# canSlaveV03_16s.net
KiCad netlist of a schematic drawn in EAGLE
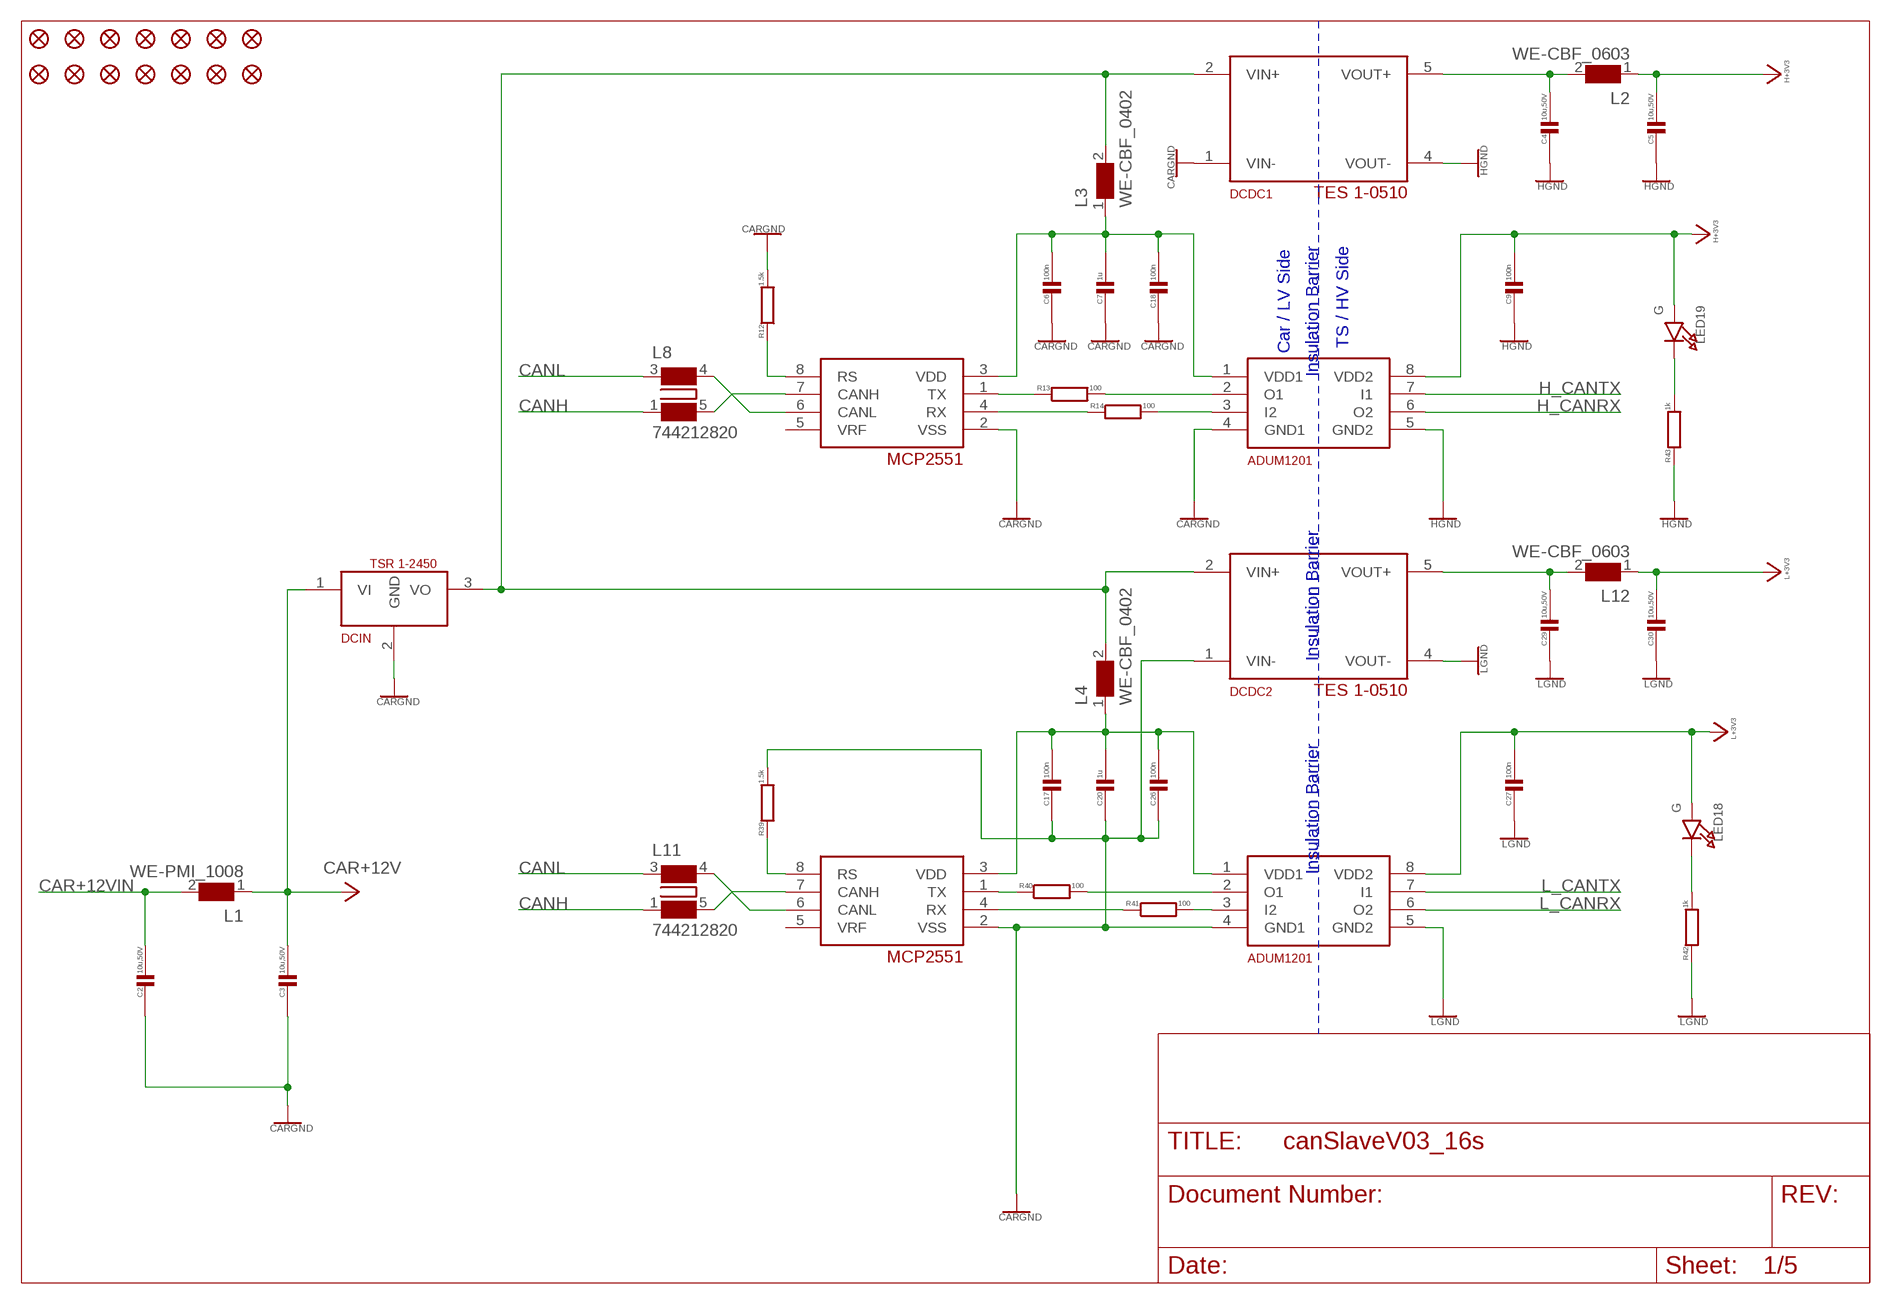
[diagram p0: schematic, sheet 1]
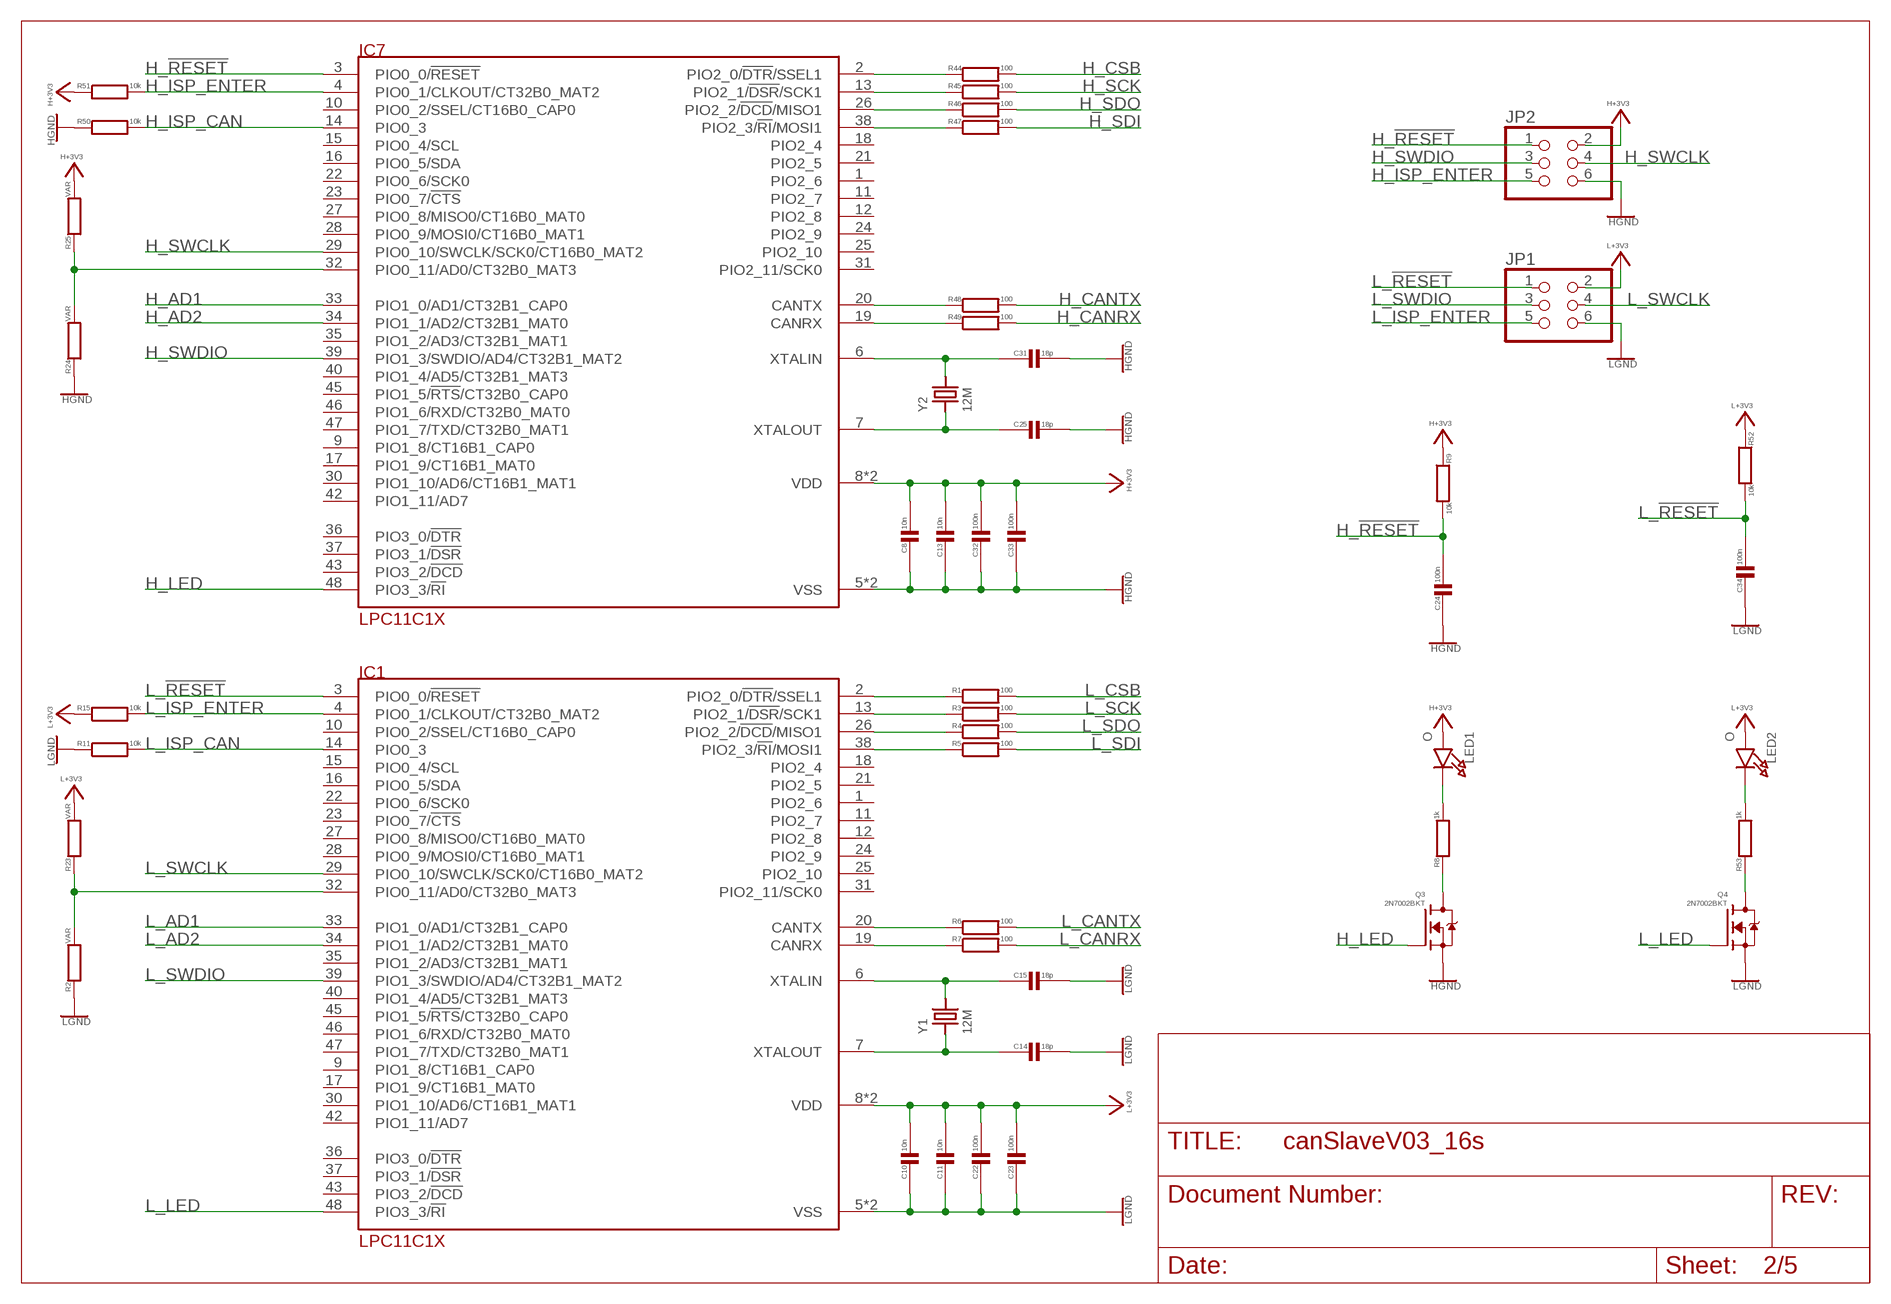
[diagram p1: schematic, sheet 2]
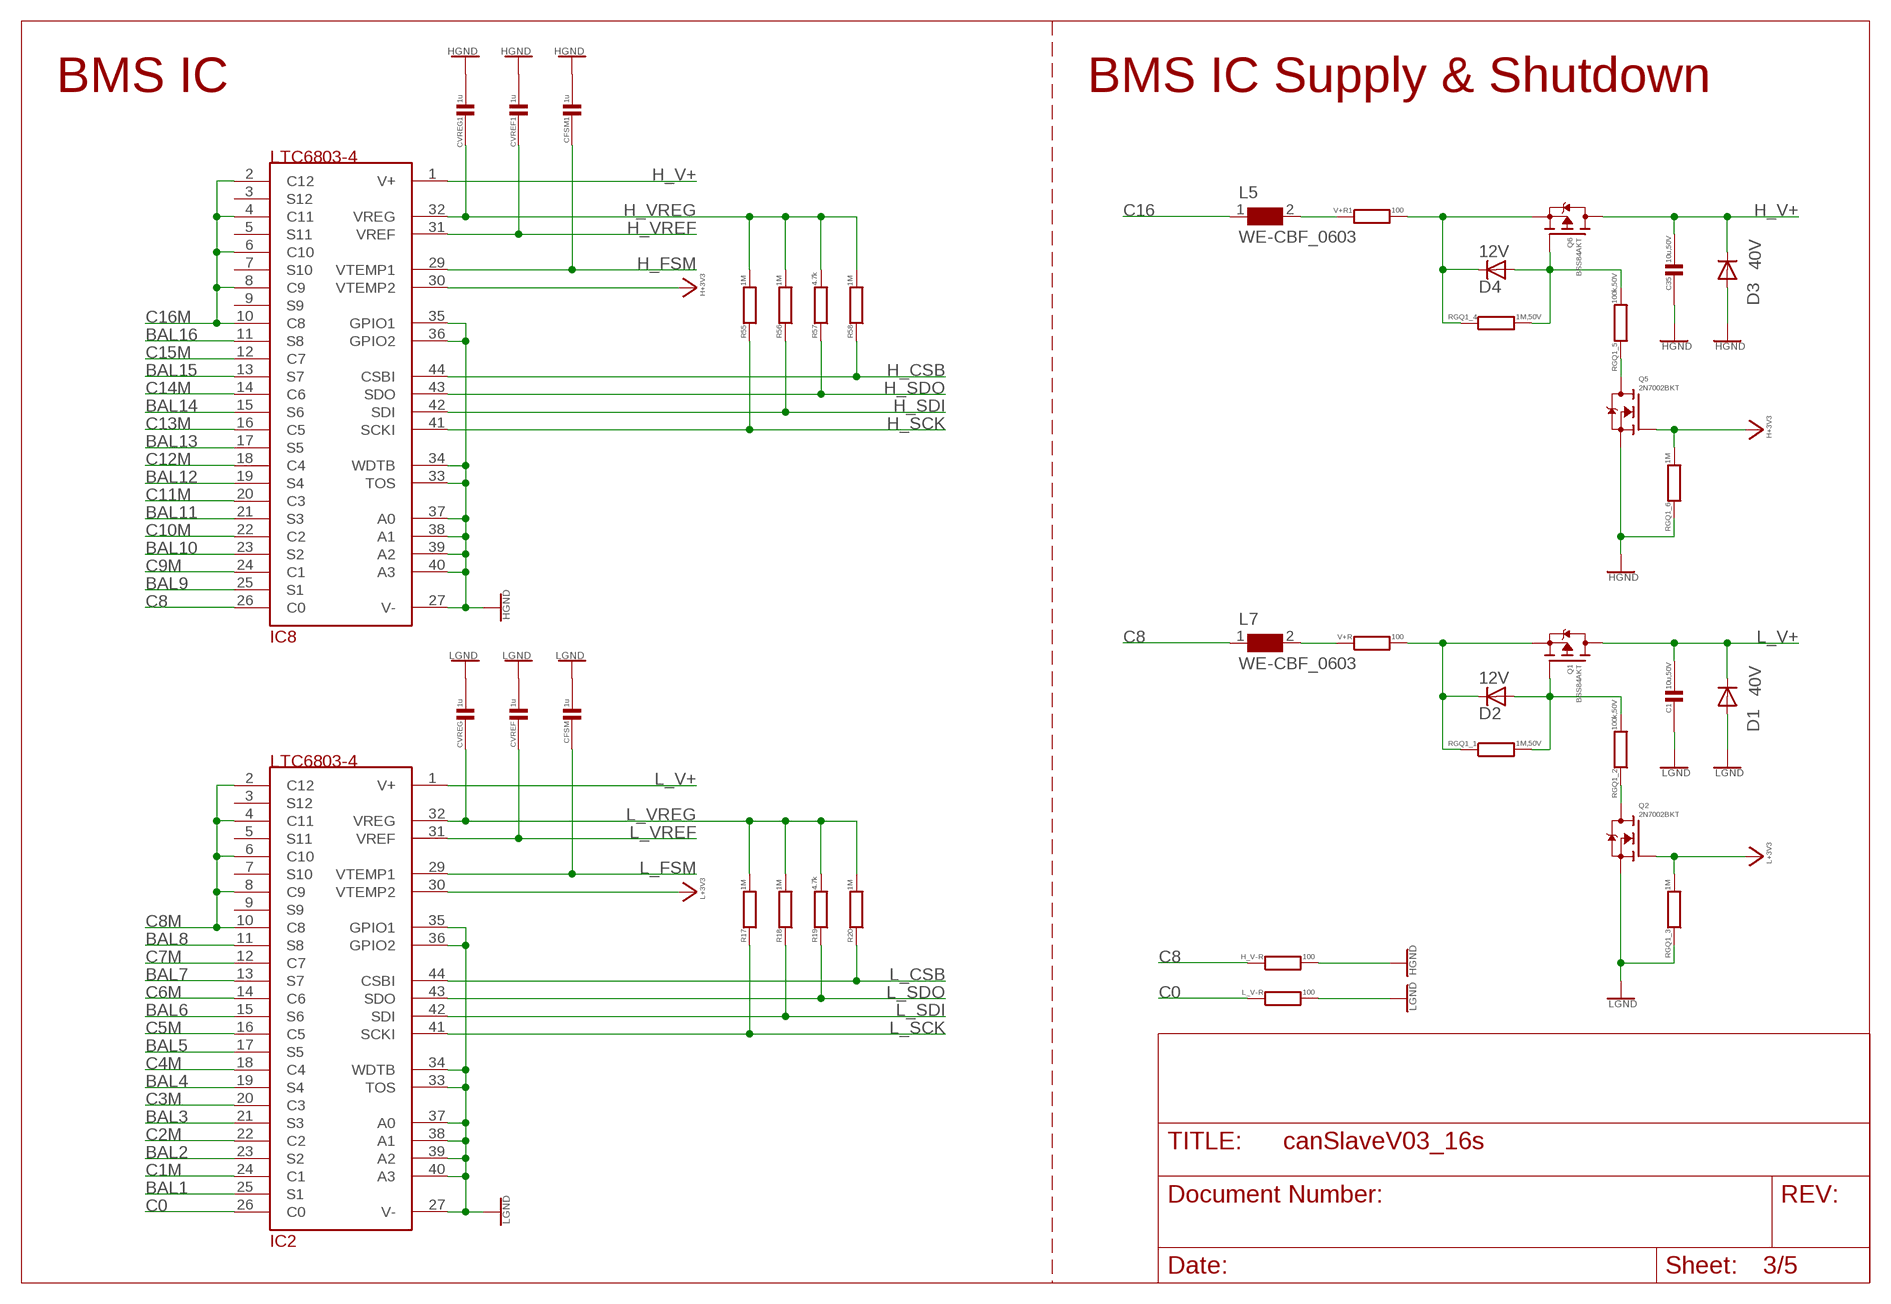
[diagram p2: schematic, sheet 3]
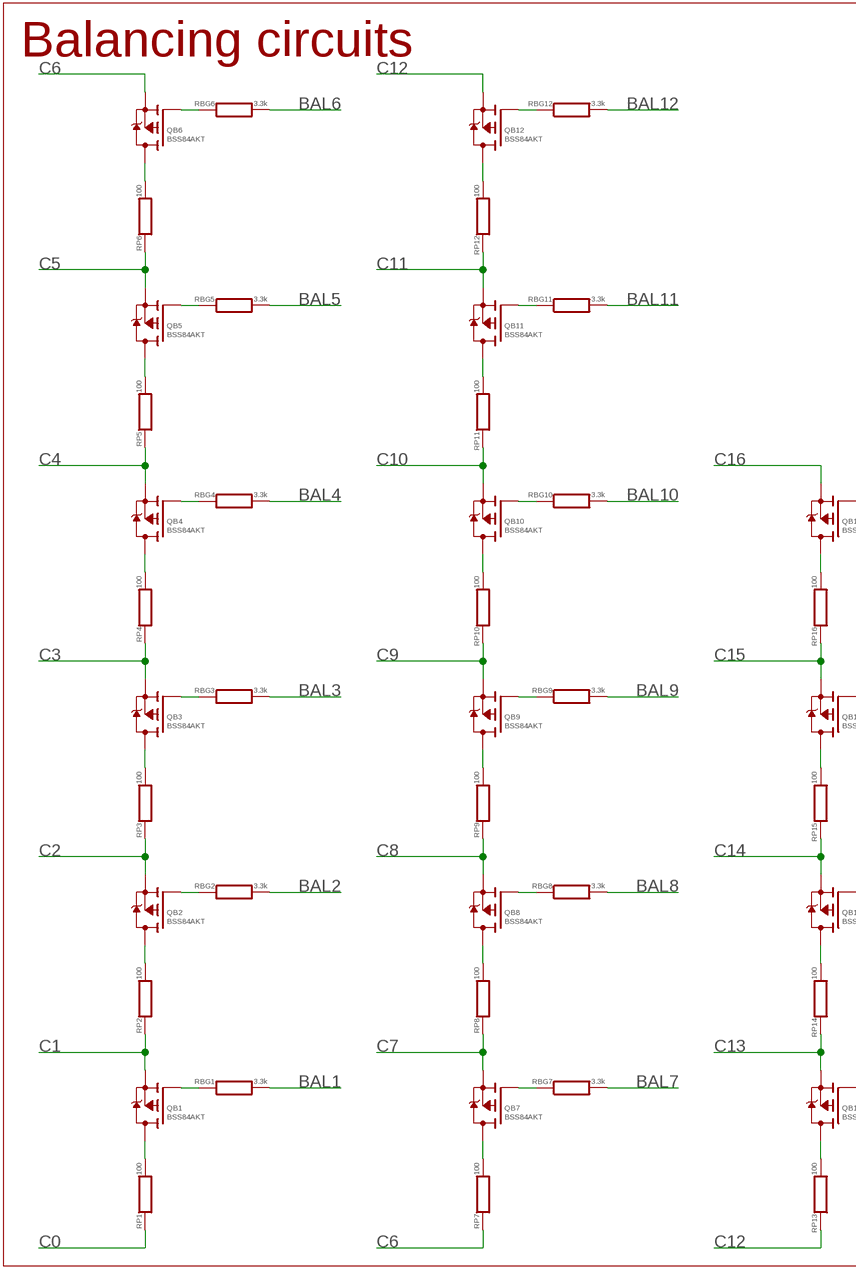
[diagram p3: schematic, sheet 4, part 1 of 2]
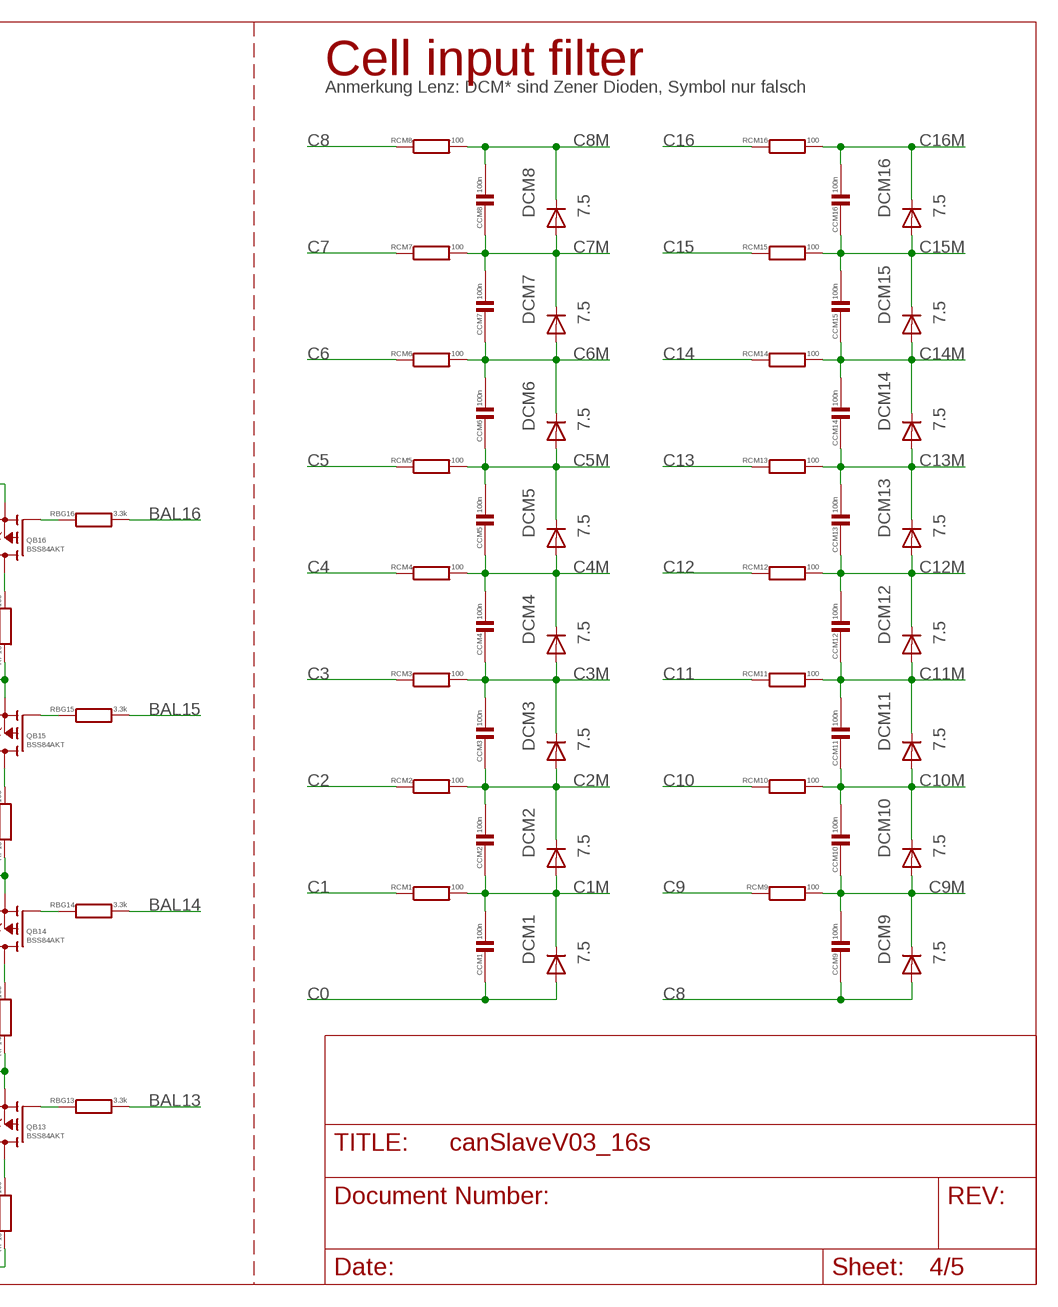
[diagram p4: schematic, sheet 4, part 2 of 2]
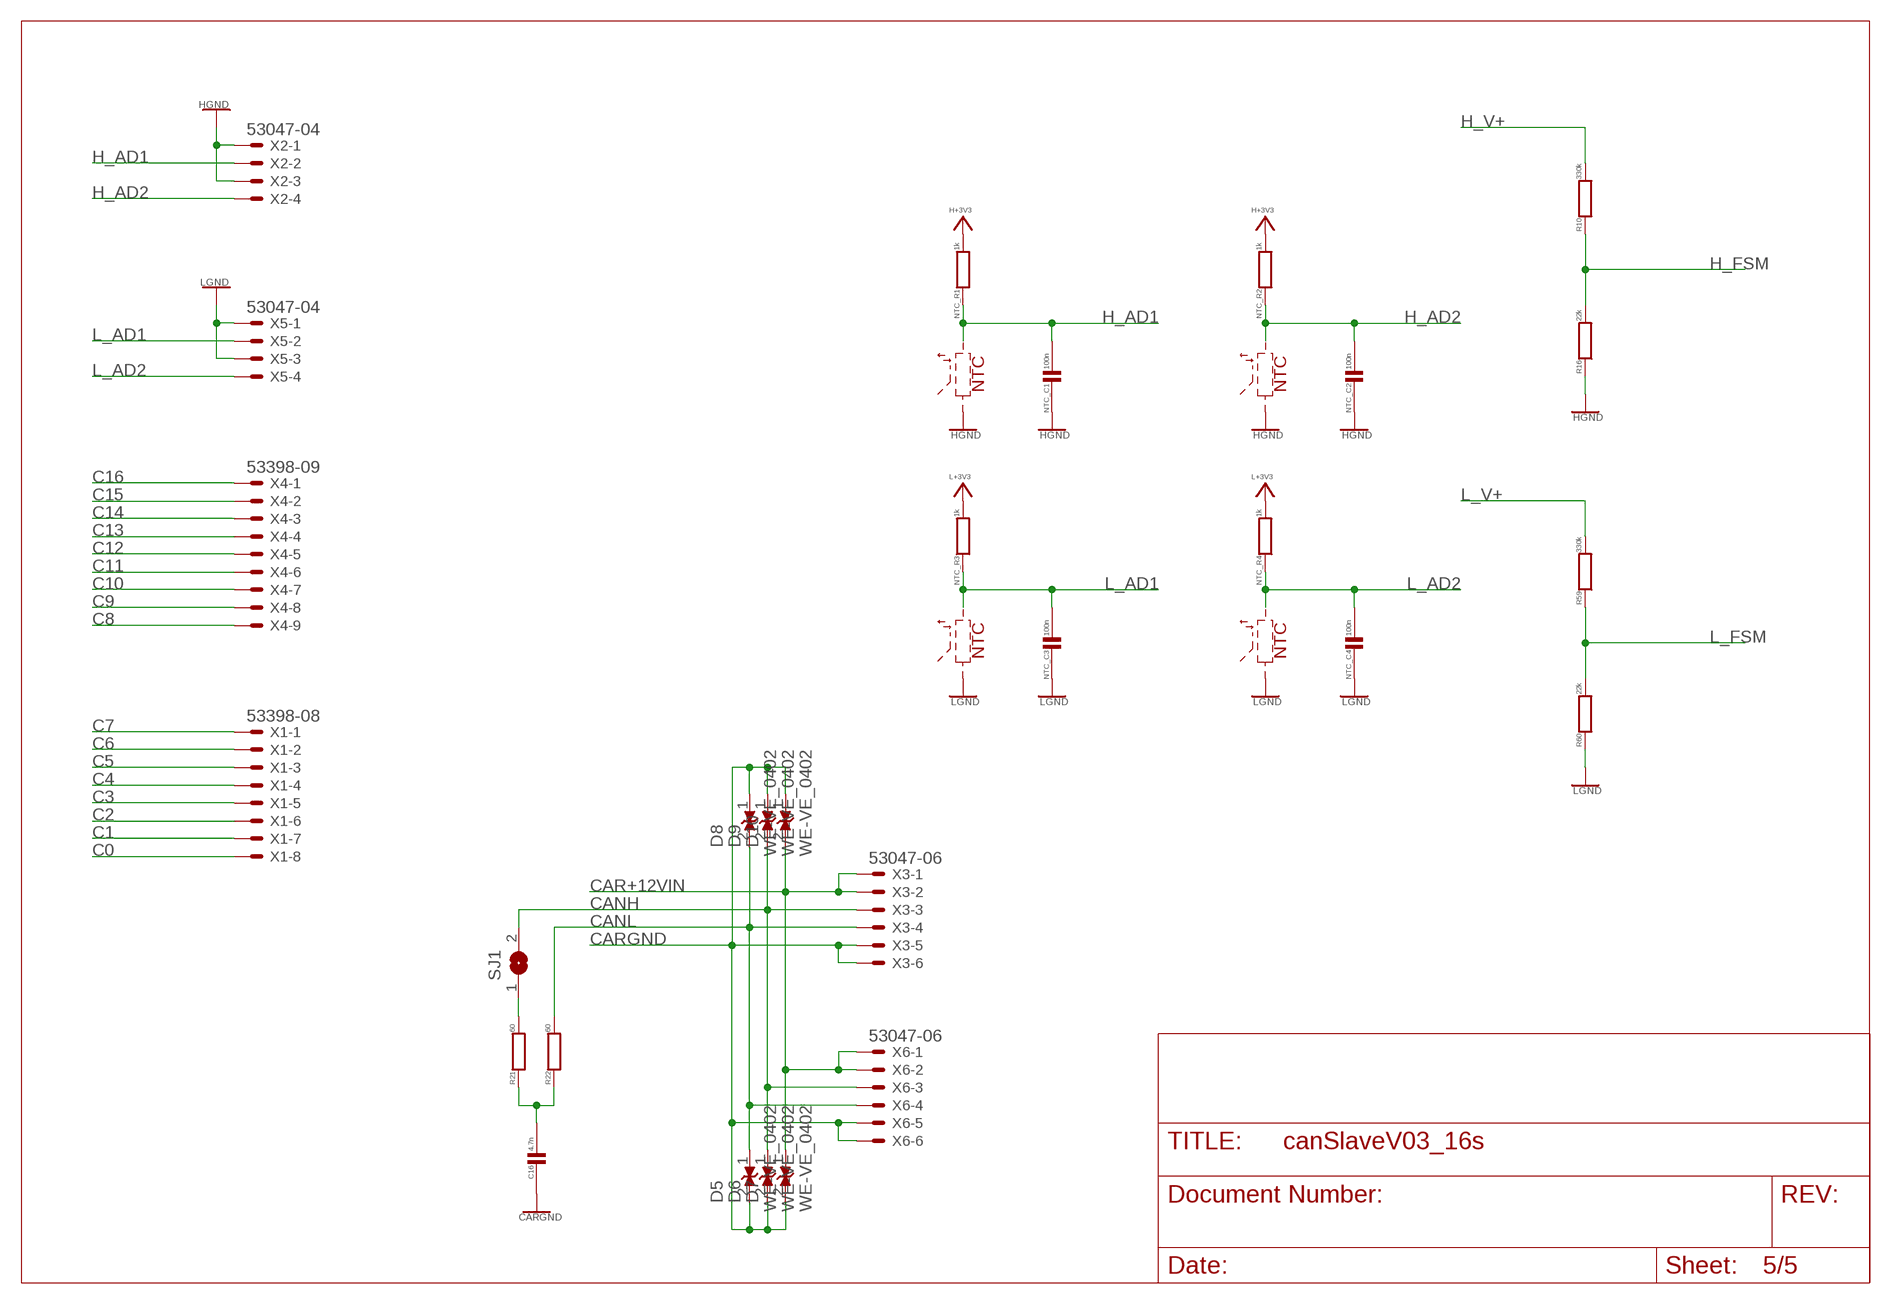
[diagram p5: schematic, sheet 5]

(export (version "E")
  (design (tool "Eeschema 10.0.6"))
  (components
    (comp (ref "C1")
      (value "10u,50V")
      (footprint "eagle-import:C1206")
      (libsource (lib "eagle-import") (part "C1206"))
    )
    (comp (ref "C35")
      (value "10u,50V")
      (footprint "eagle-import:C1206")
      (libsource (lib "eagle-import") (part "C1206"))
    )
    (comp (ref "CFSM")
      (value "1u")
      (footprint "eagle-import:C0402")
      (libsource (lib "eagle-import") (part "C0402"))
    )
    (comp (ref "CFSM1")
      (value "1u")
      (footprint "eagle-import:C0402")
      (libsource (lib "eagle-import") (part "C0402"))
    )
    (comp (ref "CVREF")
      (value "1u")
      (footprint "eagle-import:C0402")
      (libsource (lib "eagle-import") (part "C0402"))
    )
    (comp (ref "CVREF1")
      (value "1u")
      (footprint "eagle-import:C0402")
      (libsource (lib "eagle-import") (part "C0402"))
    )
    (comp (ref "CVREG")
      (value "1u")
      (footprint "eagle-import:C0402")
      (libsource (lib "eagle-import") (part "C0402"))
    )
    (comp (ref "CVREG1")
      (value "1u")
      (footprint "eagle-import:C0402")
      (libsource (lib "eagle-import") (part "C0402"))
    )
    (comp (ref "D1")
      (value "40V")
      (footprint "eagle-import:SOD323-R")
      (libsource (lib "eagle-import") (part "DIODE-SOD323-R"))
    )
    (comp (ref "D2")
      (value "12V")
      (footprint "eagle-import:SOD323-R")
      (libsource (lib "eagle-import") (part "DIODE-SOD323-R"))
    )
    (comp (ref "D3")
      (value "40V")
      (footprint "eagle-import:SOD323-R")
      (libsource (lib "eagle-import") (part "DIODE-SOD323-R"))
    )
    (comp (ref "D4")
      (value "12V")
      (footprint "eagle-import:SOD323-R")
      (libsource (lib "eagle-import") (part "DIODE-SOD323-R"))
    )
    (comp (ref "H_V-R")
      (value "100")
      (footprint "eagle-import:R0402")
      (libsource (lib "eagle-import") (part "R0402"))
    )
    (comp (ref "IC2")
      (value "LTC6803-4")
      (footprint "eagle-import:44SSOP")
      (libsource (lib "eagle-import") (part "LTC6803-4"))
    )
    (comp (ref "IC8")
      (value "LTC6803-4")
      (footprint "eagle-import:44SSOP")
      (libsource (lib "eagle-import") (part "LTC6803-4"))
    )
    (comp (ref "L5")
      (value "WE-CBF_0603")
      (footprint "eagle-import:0603")
      (libsource (lib "eagle-import") (part "WE-CBF_0603"))
    )
    (comp (ref "L7")
      (value "WE-CBF_0603")
      (footprint "eagle-import:0603")
      (libsource (lib "eagle-import") (part "WE-CBF_0603"))
    )
    (comp (ref "L_V-R")
      (value "100")
      (footprint "eagle-import:R0402")
      (libsource (lib "eagle-import") (part "R0402"))
    )
    (comp (ref "Q1")
      (value "BSS84AKT")
      (footprint "eagle-import:SOT416")
      (libsource (lib "eagle-import") (part "BSS84AKT"))
    )
    (comp (ref "Q2")
      (value "2N7002BKT")
      (footprint "eagle-import:SOT416")
      (libsource (lib "eagle-import") (part "2N7002BKT"))
    )
    (comp (ref "Q5")
      (value "2N7002BKT")
      (footprint "eagle-import:SOT416")
      (libsource (lib "eagle-import") (part "2N7002BKT"))
    )
    (comp (ref "Q6")
      (value "BSS84AKT")
      (footprint "eagle-import:SOT416")
      (libsource (lib "eagle-import") (part "BSS84AKT"))
    )
    (comp (ref "R17")
      (value "1M")
      (footprint "eagle-import:R0402")
      (libsource (lib "eagle-import") (part "R0402"))
    )
    (comp (ref "R18")
      (value "1M")
      (footprint "eagle-import:R0402")
      (libsource (lib "eagle-import") (part "R0402"))
    )
    (comp (ref "R19")
      (value "4.7k")
      (footprint "eagle-import:R0402")
      (libsource (lib "eagle-import") (part "R0402"))
    )
    (comp (ref "R20")
      (value "1M")
      (footprint "eagle-import:R0402")
      (libsource (lib "eagle-import") (part "R0402"))
    )
    (comp (ref "R55")
      (value "1M")
      (footprint "eagle-import:R0402")
      (libsource (lib "eagle-import") (part "R0402"))
    )
    (comp (ref "R56")
      (value "1M")
      (footprint "eagle-import:R0402")
      (libsource (lib "eagle-import") (part "R0402"))
    )
    (comp (ref "R57")
      (value "4.7k")
      (footprint "eagle-import:R0402")
      (libsource (lib "eagle-import") (part "R0402"))
    )
    (comp (ref "R58")
      (value "1M")
      (footprint "eagle-import:R0402")
      (libsource (lib "eagle-import") (part "R0402"))
    )
    (comp (ref "RGQ1_1")
      (value "1M,50V")
      (footprint "eagle-import:R0603")
      (libsource (lib "eagle-import") (part "R0603"))
    )
    (comp (ref "RGQ1_2")
      (value "100k,50V")
      (footprint "eagle-import:R0603")
      (libsource (lib "eagle-import") (part "R0603"))
    )
    (comp (ref "RGQ1_3")
      (value "1M")
      (footprint "eagle-import:R0402")
      (libsource (lib "eagle-import") (part "R0402"))
    )
    (comp (ref "RGQ1_4")
      (value "1M,50V")
      (footprint "eagle-import:R0603")
      (libsource (lib "eagle-import") (part "R0603"))
    )
    (comp (ref "RGQ1_5")
      (value "100k,50V")
      (footprint "eagle-import:R0603")
      (libsource (lib "eagle-import") (part "R0603"))
    )
    (comp (ref "RGQ1_6")
      (value "1M")
      (footprint "eagle-import:R0402")
      (libsource (lib "eagle-import") (part "R0402"))
    )
    (comp (ref "V+R")
      (value "100")
      (footprint "eagle-import:R0402")
      (libsource (lib "eagle-import") (part "R0402"))
    )
    (comp (ref "V+R1")
      (value "100")
      (footprint "eagle-import:R0402")
      (libsource (lib "eagle-import") (part "R0402"))
    )
    (comp (ref "C8")
      (value "10n")
      (footprint "eagle-import:C0402")
      (libsource (lib "eagle-import") (part "C0402"))
    )
    (comp (ref "C10")
      (value "10n")
      (footprint "eagle-import:C0402")
      (libsource (lib "eagle-import") (part "C0402"))
    )
    (comp (ref "C11")
      (value "10n")
      (footprint "eagle-import:C0402")
      (libsource (lib "eagle-import") (part "C0402"))
    )
    (comp (ref "C13")
      (value "10n")
      (footprint "eagle-import:C0402")
      (libsource (lib "eagle-import") (part "C0402"))
    )
    (comp (ref "C14")
      (value "18p")
      (footprint "eagle-import:C0402")
      (libsource (lib "eagle-import") (part "C0402"))
    )
    (comp (ref "C15")
      (value "18p")
      (footprint "eagle-import:C0402")
      (libsource (lib "eagle-import") (part "C0402"))
    )
    (comp (ref "C22")
      (value "100n")
      (footprint "eagle-import:C0402")
      (libsource (lib "eagle-import") (part "C0402"))
    )
    (comp (ref "C23")
      (value "100n")
      (footprint "eagle-import:C0402")
      (libsource (lib "eagle-import") (part "C0402"))
    )
    (comp (ref "C24")
      (value "100n")
      (footprint "eagle-import:C0402")
      (libsource (lib "eagle-import") (part "C0402"))
    )
    (comp (ref "C25")
      (value "18p")
      (footprint "eagle-import:C0402")
      (libsource (lib "eagle-import") (part "C0402"))
    )
    (comp (ref "C31")
      (value "18p")
      (footprint "eagle-import:C0402")
      (libsource (lib "eagle-import") (part "C0402"))
    )
    (comp (ref "C32")
      (value "100n")
      (footprint "eagle-import:C0402")
      (libsource (lib "eagle-import") (part "C0402"))
    )
    (comp (ref "C33")
      (value "100n")
      (footprint "eagle-import:C0402")
      (libsource (lib "eagle-import") (part "C0402"))
    )
    (comp (ref "C34")
      (value "100n")
      (footprint "eagle-import:C0402")
      (libsource (lib "eagle-import") (part "C0402"))
    )
    (comp (ref "IC1")
      (value "LPC11C1X")
      (footprint "eagle-import:LQFP48")
      (libsource (lib "eagle-import") (part "LPC11C1X"))
    )
    (comp (ref "IC7")
      (value "LPC11C1X")
      (footprint "eagle-import:LQFP48")
      (libsource (lib "eagle-import") (part "LPC11C1X"))
    )
    (comp (ref "JP1")
      (value "HEADER-2X31.27")
      (footprint "eagle-import:2X03_1.27MM_SMT")
      (libsource (lib "eagle-import") (part "HEADER-2X31.27"))
    )
    (comp (ref "JP2")
      (value "HEADER-2X31.27")
      (footprint "eagle-import:2X03_1.27MM_SMT")
      (libsource (lib "eagle-import") (part "HEADER-2X31.27"))
    )
    (comp (ref "LED1")
      (value "O")
      (footprint "eagle-import:CHIPLED_0603")
      (libsource (lib "eagle-import") (part "LED0603"))
    )
    (comp (ref "LED2")
      (value "O")
      (footprint "eagle-import:CHIPLED_0603")
      (libsource (lib "eagle-import") (part "LED0603"))
    )
    (comp (ref "Q3")
      (value "2N7002BKT")
      (footprint "eagle-import:SOT416")
      (libsource (lib "eagle-import") (part "2N7002BKT"))
    )
    (comp (ref "Q4")
      (value "2N7002BKT")
      (footprint "eagle-import:SOT416")
      (libsource (lib "eagle-import") (part "2N7002BKT"))
    )
    (comp (ref "R1")
      (value "100")
      (footprint "eagle-import:R0402")
      (libsource (lib "eagle-import") (part "R0402"))
    )
    (comp (ref "R2")
      (value "VAR")
      (footprint "eagle-import:R0402")
      (libsource (lib "eagle-import") (part "R0402"))
    )
    (comp (ref "R3")
      (value "100")
      (footprint "eagle-import:R0402")
      (libsource (lib "eagle-import") (part "R0402"))
    )
    (comp (ref "R4")
      (value "100")
      (footprint "eagle-import:R0402")
      (libsource (lib "eagle-import") (part "R0402"))
    )
    (comp (ref "R5")
      (value "100")
      (footprint "eagle-import:R0402")
      (libsource (lib "eagle-import") (part "R0402"))
    )
    (comp (ref "R6")
      (value "100")
      (footprint "eagle-import:R0402")
      (libsource (lib "eagle-import") (part "R0402"))
    )
    (comp (ref "R7")
      (value "100")
      (footprint "eagle-import:R0402")
      (libsource (lib "eagle-import") (part "R0402"))
    )
    (comp (ref "R8")
      (value "1k")
      (footprint "eagle-import:R0603")
      (libsource (lib "eagle-import") (part "R0603"))
    )
    (comp (ref "R9")
      (value "10k")
      (footprint "eagle-import:R0402")
      (libsource (lib "eagle-import") (part "R0402"))
    )
    (comp (ref "R11")
      (value "10k")
      (footprint "eagle-import:R0402")
      (libsource (lib "eagle-import") (part "R0402"))
    )
    (comp (ref "R15")
      (value "10k")
      (footprint "eagle-import:R0402")
      (libsource (lib "eagle-import") (part "R0402"))
    )
    (comp (ref "R23")
      (value "VAR")
      (footprint "eagle-import:R0402")
      (libsource (lib "eagle-import") (part "R0402"))
    )
    (comp (ref "R24")
      (value "VAR")
      (footprint "eagle-import:R0402")
      (libsource (lib "eagle-import") (part "R0402"))
    )
    (comp (ref "R25")
      (value "VAR")
      (footprint "eagle-import:R0402")
      (libsource (lib "eagle-import") (part "R0402"))
    )
    (comp (ref "R44")
      (value "100")
      (footprint "eagle-import:R0402")
      (libsource (lib "eagle-import") (part "R0402"))
    )
    (comp (ref "R45")
      (value "100")
      (footprint "eagle-import:R0402")
      (libsource (lib "eagle-import") (part "R0402"))
    )
    (comp (ref "R46")
      (value "100")
      (footprint "eagle-import:R0402")
      (libsource (lib "eagle-import") (part "R0402"))
    )
    (comp (ref "R47")
      (value "100")
      (footprint "eagle-import:R0402")
      (libsource (lib "eagle-import") (part "R0402"))
    )
    (comp (ref "R48")
      (value "100")
      (footprint "eagle-import:R0402")
      (libsource (lib "eagle-import") (part "R0402"))
    )
    (comp (ref "R49")
      (value "100")
      (footprint "eagle-import:R0402")
      (libsource (lib "eagle-import") (part "R0402"))
    )
    (comp (ref "R50")
      (value "10k")
      (footprint "eagle-import:R0402")
      (libsource (lib "eagle-import") (part "R0402"))
    )
    (comp (ref "R51")
      (value "10k")
      (footprint "eagle-import:R0402")
      (libsource (lib "eagle-import") (part "R0402"))
    )
    (comp (ref "R52")
      (value "10k")
      (footprint "eagle-import:R0402")
      (libsource (lib "eagle-import") (part "R0402"))
    )
    (comp (ref "R53")
      (value "1k")
      (footprint "eagle-import:R0603")
      (libsource (lib "eagle-import") (part "R0603"))
    )
    (comp (ref "Y1")
      (value "12M")
      (footprint "eagle-import:CRYSTAL_3.2X2.5")
      (libsource (lib "eagle-import") (part "CRYSTALTHIN"))
    )
    (comp (ref "Y2")
      (value "12M")
      (footprint "eagle-import:CRYSTAL_3.2X2.5")
      (libsource (lib "eagle-import") (part "CRYSTALTHIN"))
    )
    (comp (ref "C16")
      (value "4.7n")
      (footprint "eagle-import:C0402")
      (libsource (lib "eagle-import") (part "C0402"))
    )
    (comp (ref "D5")
      (value "WE-VE_0402")
      (footprint "eagle-import:WESURGE_0402")
      (libsource (lib "eagle-import") (part "WE-VE_0402"))
    )
    (comp (ref "D6")
      (value "WE-VE_0402")
      (footprint "eagle-import:WESURGE_0402")
      (libsource (lib "eagle-import") (part "WE-VE_0402"))
    )
    (comp (ref "D7")
      (value "WE-VE_0402")
      (footprint "eagle-import:WESURGE_0402")
      (libsource (lib "eagle-import") (part "WE-VE_0402"))
    )
    (comp (ref "D8")
      (value "WE-VE_0402")
      (footprint "eagle-import:WESURGE_0402")
      (libsource (lib "eagle-import") (part "WE-VE_0402"))
    )
    (comp (ref "D9")
      (value "WE-VE_0402")
      (footprint "eagle-import:WESURGE_0402")
      (libsource (lib "eagle-import") (part "WE-VE_0402"))
    )
    (comp (ref "D10")
      (value "WE-VE_0402")
      (footprint "eagle-import:WESURGE_0402")
      (libsource (lib "eagle-import") (part "WE-VE_0402"))
    )
    (comp (ref "NTC_C1")
      (value "100n")
      (footprint "eagle-import:C0402")
      (libsource (lib "eagle-import") (part "C0402"))
    )
    (comp (ref "NTC_C2")
      (value "100n")
      (footprint "eagle-import:C0402")
      (libsource (lib "eagle-import") (part "C0402"))
    )
    (comp (ref "NTC_C3")
      (value "100n")
      (footprint "eagle-import:C0402")
      (libsource (lib "eagle-import") (part "C0402"))
    )
    (comp (ref "NTC_C4")
      (value "100n")
      (footprint "eagle-import:C0402")
      (libsource (lib "eagle-import") (part "C0402"))
    )
    (comp (ref "NTC_R1")
      (value "1k")
      (footprint "eagle-import:R0402")
      (libsource (lib "eagle-import") (part "R0402"))
    )
    (comp (ref "NTC_R2")
      (value "1k")
      (footprint "eagle-import:R0402")
      (libsource (lib "eagle-import") (part "R0402"))
    )
    (comp (ref "NTC_R3")
      (value "1k")
      (footprint "eagle-import:R0402")
      (libsource (lib "eagle-import") (part "R0402"))
    )
    (comp (ref "NTC_R4")
      (value "1k")
      (footprint "eagle-import:R0402")
      (libsource (lib "eagle-import") (part "R0402"))
    )
    (comp (ref "R10")
      (value "330k")
      (footprint "eagle-import:R0603")
      (libsource (lib "eagle-import") (part "R0603"))
    )
    (comp (ref "R16")
      (value "22k")
      (footprint "eagle-import:R0603")
      (libsource (lib "eagle-import") (part "R0603"))
    )
    (comp (ref "R21")
      (value "60")
      (footprint "eagle-import:R0402")
      (libsource (lib "eagle-import") (part "R0402"))
    )
    (comp (ref "R22")
      (value "60")
      (footprint "eagle-import:R0402")
      (libsource (lib "eagle-import") (part "R0402"))
    )
    (comp (ref "R59")
      (value "330k")
      (footprint "eagle-import:R0603")
      (libsource (lib "eagle-import") (part "R0603"))
    )
    (comp (ref "R60")
      (value "22k")
      (footprint "eagle-import:R0603")
      (libsource (lib "eagle-import") (part "R0603"))
    )
    (comp (ref "SJ1")
      (value "SOLDERJUMPERSMALL")
      (footprint "eagle-import:SOLDERJUMPER_REFLOW_NOPASTE_SMALL")
      (libsource (lib "eagle-import") (part "SOLDERJUMPERSMALL"))
    )
    (comp (ref "X1")
      (value "53398-08")
      (footprint "eagle-import:53398-08")
      (libsource (lib "eagle-import") (part "53?-08398"))
    )
    (comp (ref "X2")
      (value "53047-04")
      (footprint "eagle-import:53047-04")
      (fields
        (field (name "MF") "WALDOM/MOLEX")
        (field (name "MPN") "53047-0410")
        (field (name "MF_1") "WALDOM/MOLEX")
        (field (name "MPN_1") "53047-0410")
        (field (name "OC_FARNELL") "9733060")
        (field (name "OC_NEWARK") "38C9900")
      )
      (libsource (lib "eagle-import") (part "53?-04047"))
    )
    (comp (ref "X3")
      (value "53047-06")
      (footprint "eagle-import:53047-06")
      (fields (field (name "MPN") "53047-0610-C"))
      (libsource (lib "eagle-import") (part "53?-06047"))
    )
    (comp (ref "X4")
      (value "53398-09")
      (footprint "eagle-import:53398-09")
      (libsource (lib "eagle-import") (part "53?-09398"))
    )
    (comp (ref "X5")
      (value "53047-04")
      (footprint "eagle-import:53047-04")
      (fields
        (field (name "MF") "WALDOM/MOLEX")
        (field (name "MPN") "53047-0410")
        (field (name "MF_1") "WALDOM/MOLEX")
        (field (name "MPN_1") "53047-0410")
        (field (name "OC_FARNELL") "9733060")
        (field (name "OC_NEWARK") "38C9900")
      )
      (libsource (lib "eagle-import") (part "53?-04047"))
    )
    (comp (ref "X6")
      (value "53047-06")
      (footprint "eagle-import:53047-06")
      (fields (field (name "MPN") "53047-0610-C"))
      (libsource (lib "eagle-import") (part "53?-06047"))
    )
    (comp (ref "C2")
      (value "10u,50V")
      (footprint "eagle-import:C0603")
      (libsource (lib "eagle-import") (part "C0603"))
    )
    (comp (ref "C3")
      (value "10u,50V")
      (footprint "eagle-import:C0603")
      (libsource (lib "eagle-import") (part "C0603"))
    )
    (comp (ref "C4")
      (value "10u,50V")
      (footprint "eagle-import:C0603")
      (libsource (lib "eagle-import") (part "C0603"))
    )
    (comp (ref "C5")
      (value "10u,50V")
      (footprint "eagle-import:C0603")
      (libsource (lib "eagle-import") (part "C0603"))
    )
    (comp (ref "C6")
      (value "100n")
      (footprint "eagle-import:C0402")
      (libsource (lib "eagle-import") (part "C0402"))
    )
    (comp (ref "C7")
      (value "1u")
      (footprint "eagle-import:C0402")
      (libsource (lib "eagle-import") (part "C0402"))
    )
    (comp (ref "C9")
      (value "100n")
      (footprint "eagle-import:C0402")
      (libsource (lib "eagle-import") (part "C0402"))
    )
    (comp (ref "C17")
      (value "100n")
      (footprint "eagle-import:C0402")
      (libsource (lib "eagle-import") (part "C0402"))
    )
    (comp (ref "C18")
      (value "100n")
      (footprint "eagle-import:C0402")
      (libsource (lib "eagle-import") (part "C0402"))
    )
    (comp (ref "C20")
      (value "1u")
      (footprint "eagle-import:C0402")
      (libsource (lib "eagle-import") (part "C0402"))
    )
    (comp (ref "C26")
      (value "100n")
      (footprint "eagle-import:C0402")
      (libsource (lib "eagle-import") (part "C0402"))
    )
    (comp (ref "C27")
      (value "100n")
      (footprint "eagle-import:C0402")
      (libsource (lib "eagle-import") (part "C0402"))
    )
    (comp (ref "C29")
      (value "10u,50V")
      (footprint "eagle-import:C0603")
      (libsource (lib "eagle-import") (part "C0603"))
    )
    (comp (ref "C30")
      (value "10u,50V")
      (footprint "eagle-import:C0603")
      (libsource (lib "eagle-import") (part "C0603"))
    )
    (comp (ref "DCDC1")
      (value "TES 1-0510")
      (footprint "eagle-import:ISF")
      (libsource (lib "eagle-import") (part "ISFXXXXA"))
    )
    (comp (ref "DCDC2")
      (value "TES 1-0510")
      (footprint "eagle-import:ISF")
      (libsource (lib "eagle-import") (part "ISFXXXXA"))
    )
    (comp (ref "DCIN")
      (value "TSR 1-2450")
      (footprint "eagle-import:TSR1")
      (libsource (lib "eagle-import") (part "TSR1"))
    )
    (comp (ref "FID1")
      (value "FIDUCIAL\"\"")
      (footprint "eagle-import:FIDUCIAL_1MM")
      (libsource (lib "eagle-import") (part "FIDUCIAL{dblquote}{dblquote}"))
    )
    (comp (ref "FID2")
      (value "FIDUCIAL\"\"")
      (footprint "eagle-import:FIDUCIAL_1MM")
      (libsource (lib "eagle-import") (part "FIDUCIAL{dblquote}{dblquote}"))
    )
    (comp (ref "FID3")
      (value "FIDUCIAL\"\"")
      (footprint "eagle-import:FIDUCIAL_1MM")
      (libsource (lib "eagle-import") (part "FIDUCIAL{dblquote}{dblquote}"))
    )
    (comp (ref "FID4")
      (value "FIDUCIAL\"\"")
      (footprint "eagle-import:FIDUCIAL_1MM")
      (libsource (lib "eagle-import") (part "FIDUCIAL{dblquote}{dblquote}"))
    )
    (comp (ref "FID5")
      (value "FIDUCIAL\"\"")
      (footprint "eagle-import:FIDUCIAL_1MM")
      (libsource (lib "eagle-import") (part "FIDUCIAL{dblquote}{dblquote}"))
    )
    (comp (ref "FID6")
      (value "FIDUCIAL\"\"")
      (footprint "eagle-import:FIDUCIAL_1MM")
      (libsource (lib "eagle-import") (part "FIDUCIAL{dblquote}{dblquote}"))
    )
    (comp (ref "FID7")
      (value "FIDUCIAL\"\"")
      (footprint "eagle-import:FIDUCIAL_1MM")
      (libsource (lib "eagle-import") (part "FIDUCIAL{dblquote}{dblquote}"))
    )
    (comp (ref "FID8")
      (value "FIDUCIAL\"\"")
      (footprint "eagle-import:FIDUCIAL_1MM")
      (libsource (lib "eagle-import") (part "FIDUCIAL{dblquote}{dblquote}"))
    )
    (comp (ref "FID9")
      (value "FIDUCIAL\"\"")
      (footprint "eagle-import:FIDUCIAL_1MM")
      (libsource (lib "eagle-import") (part "FIDUCIAL{dblquote}{dblquote}"))
    )
    (comp (ref "FID10")
      (value "FIDUCIAL\"\"")
      (footprint "eagle-import:FIDUCIAL_1MM")
      (libsource (lib "eagle-import") (part "FIDUCIAL{dblquote}{dblquote}"))
    )
    (comp (ref "FID11")
      (value "FIDUCIAL\"\"")
      (footprint "eagle-import:FIDUCIAL_1MM")
      (libsource (lib "eagle-import") (part "FIDUCIAL{dblquote}{dblquote}"))
    )
    (comp (ref "FID12")
      (value "FIDUCIAL\"\"")
      (footprint "eagle-import:FIDUCIAL_1MM")
      (libsource (lib "eagle-import") (part "FIDUCIAL{dblquote}{dblquote}"))
    )
    (comp (ref "FID13")
      (value "FIDUCIAL\"\"")
      (footprint "eagle-import:FIDUCIAL_1MM")
      (libsource (lib "eagle-import") (part "FIDUCIAL{dblquote}{dblquote}"))
    )
    (comp (ref "FID14")
      (value "FIDUCIAL\"\"")
      (footprint "eagle-import:FIDUCIAL_1MM")
      (libsource (lib "eagle-import") (part "FIDUCIAL{dblquote}{dblquote}"))
    )
    (comp (ref "IC3")
      (value "ADUM1201")
      (footprint "eagle-import:SO-8")
      (libsource (lib "eagle-import") (part "ADUM1201"))
    )
    (comp (ref "IC4")
      (value "MCP2551")
      (footprint "eagle-import:SO-8")
      (libsource (lib "eagle-import") (part "MCP2551"))
    )
    (comp (ref "IC5")
      (value "MCP2551")
      (footprint "eagle-import:SO-8")
      (libsource (lib "eagle-import") (part "MCP2551"))
    )
    (comp (ref "IC6")
      (value "ADUM1201")
      (footprint "eagle-import:SO-8")
      (libsource (lib "eagle-import") (part "ADUM1201"))
    )
    (comp (ref "L1")
      (value "WE-PMI_1008")
      (footprint "eagle-import:WE-PMI_1008")
      (libsource (lib "eagle-import") (part "WE-PMI_1008"))
    )
    (comp (ref "L2")
      (value "WE-CBF_0603")
      (footprint "eagle-import:0603")
      (libsource (lib "eagle-import") (part "WE-CBF_0603"))
    )
    (comp (ref "L3")
      (value "WE-CBF_0402")
      (footprint "eagle-import:0402")
      (libsource (lib "eagle-import") (part "WE-CBF_0402"))
    )
    (comp (ref "L4")
      (value "WE-CBF_0402")
      (footprint "eagle-import:0402")
      (libsource (lib "eagle-import") (part "WE-CBF_0402"))
    )
    (comp (ref "L8")
      (value "744212820")
      (footprint "eagle-import:WE-SL1")
      (libsource (lib "eagle-import") (part "WE-SL1"))
    )
    (comp (ref "L11")
      (value "744212820")
      (footprint "eagle-import:WE-SL1")
      (libsource (lib "eagle-import") (part "WE-SL1"))
    )
    (comp (ref "L12")
      (value "WE-CBF_0603")
      (footprint "eagle-import:0603")
      (libsource (lib "eagle-import") (part "WE-CBF_0603"))
    )
    (comp (ref "LED18")
      (value "G")
      (footprint "eagle-import:CHIPLED_0603")
      (libsource (lib "eagle-import") (part "LED0603"))
    )
    (comp (ref "LED19")
      (value "G")
      (footprint "eagle-import:CHIPLED_0603")
      (libsource (lib "eagle-import") (part "LED0603"))
    )
    (comp (ref "R12")
      (value "1.5k")
      (footprint "eagle-import:R0402")
      (libsource (lib "eagle-import") (part "R0402"))
    )
    (comp (ref "R13")
      (value "100")
      (footprint "eagle-import:R0402")
      (libsource (lib "eagle-import") (part "R0402"))
    )
    (comp (ref "R14")
      (value "100")
      (footprint "eagle-import:R0402")
      (libsource (lib "eagle-import") (part "R0402"))
    )
    (comp (ref "R39")
      (value "1.5k")
      (footprint "eagle-import:R0402")
      (libsource (lib "eagle-import") (part "R0402"))
    )
    (comp (ref "R40")
      (value "100")
      (footprint "eagle-import:R0402")
      (libsource (lib "eagle-import") (part "R0402"))
    )
    (comp (ref "R41")
      (value "100")
      (footprint "eagle-import:R0402")
      (libsource (lib "eagle-import") (part "R0402"))
    )
    (comp (ref "R42")
      (value "1k")
      (footprint "eagle-import:R0603")
      (libsource (lib "eagle-import") (part "R0603"))
    )
    (comp (ref "R43")
      (value "1k")
      (footprint "eagle-import:R0603")
      (libsource (lib "eagle-import") (part "R0603"))
    )
    (comp (ref "CCM1")
      (value "100n")
      (footprint "eagle-import:C0402")
      (libsource (lib "eagle-import") (part "C0402"))
    )
    (comp (ref "CCM2")
      (value "100n")
      (footprint "eagle-import:C0402")
      (libsource (lib "eagle-import") (part "C0402"))
    )
    (comp (ref "CCM3")
      (value "100n")
      (footprint "eagle-import:C0402")
      (libsource (lib "eagle-import") (part "C0402"))
    )
    (comp (ref "CCM4")
      (value "100n")
      (footprint "eagle-import:C0402")
      (libsource (lib "eagle-import") (part "C0402"))
    )
    (comp (ref "CCM5")
      (value "100n")
      (footprint "eagle-import:C0402")
      (libsource (lib "eagle-import") (part "C0402"))
    )
    (comp (ref "CCM6")
      (value "100n")
      (footprint "eagle-import:C0402")
      (libsource (lib "eagle-import") (part "C0402"))
    )
    (comp (ref "CCM7")
      (value "100n")
      (footprint "eagle-import:C0402")
      (libsource (lib "eagle-import") (part "C0402"))
    )
    (comp (ref "CCM8")
      (value "100n")
      (footprint "eagle-import:C0402")
      (libsource (lib "eagle-import") (part "C0402"))
    )
    (comp (ref "CCM9")
      (value "100n")
      (footprint "eagle-import:C0402")
      (libsource (lib "eagle-import") (part "C0402"))
    )
    (comp (ref "CCM10")
      (value "100n")
      (footprint "eagle-import:C0402")
      (libsource (lib "eagle-import") (part "C0402"))
    )
    (comp (ref "CCM11")
      (value "100n")
      (footprint "eagle-import:C0402")
      (libsource (lib "eagle-import") (part "C0402"))
    )
    (comp (ref "CCM12")
      (value "100n")
      (footprint "eagle-import:C0402")
      (libsource (lib "eagle-import") (part "C0402"))
    )
    (comp (ref "CCM13")
      (value "100n")
      (footprint "eagle-import:C0402")
      (libsource (lib "eagle-import") (part "C0402"))
    )
    (comp (ref "CCM14")
      (value "100n")
      (footprint "eagle-import:C0402")
      (libsource (lib "eagle-import") (part "C0402"))
    )
    (comp (ref "CCM15")
      (value "100n")
      (footprint "eagle-import:C0402")
      (libsource (lib "eagle-import") (part "C0402"))
    )
    (comp (ref "CCM16")
      (value "100n")
      (footprint "eagle-import:C0402")
      (libsource (lib "eagle-import") (part "C0402"))
    )
    (comp (ref "DCM1")
      (value "7.5")
      (footprint "eagle-import:SOD323-R")
      (libsource (lib "eagle-import") (part "DIODE-SOD323-R"))
    )
    (comp (ref "DCM2")
      (value "7.5")
      (footprint "eagle-import:SOD323-R")
      (libsource (lib "eagle-import") (part "DIODE-SOD323-R"))
    )
    (comp (ref "DCM3")
      (value "7.5")
      (footprint "eagle-import:SOD323-R")
      (libsource (lib "eagle-import") (part "DIODE-SOD323-R"))
    )
    (comp (ref "DCM4")
      (value "7.5")
      (footprint "eagle-import:SOD323-R")
      (libsource (lib "eagle-import") (part "DIODE-SOD323-R"))
    )
    (comp (ref "DCM5")
      (value "7.5")
      (footprint "eagle-import:SOD323-R")
      (libsource (lib "eagle-import") (part "DIODE-SOD323-R"))
    )
    (comp (ref "DCM6")
      (value "7.5")
      (footprint "eagle-import:SOD323-R")
      (libsource (lib "eagle-import") (part "DIODE-SOD323-R"))
    )
    (comp (ref "DCM7")
      (value "7.5")
      (footprint "eagle-import:SOD323-R")
      (libsource (lib "eagle-import") (part "DIODE-SOD323-R"))
    )
    (comp (ref "DCM8")
      (value "7.5")
      (footprint "eagle-import:SOD323-R")
      (libsource (lib "eagle-import") (part "DIODE-SOD323-R"))
    )
    (comp (ref "DCM9")
      (value "7.5")
      (footprint "eagle-import:SOD323-R")
      (libsource (lib "eagle-import") (part "DIODE-SOD323-R"))
    )
    (comp (ref "DCM10")
      (value "7.5")
      (footprint "eagle-import:SOD323-R")
      (libsource (lib "eagle-import") (part "DIODE-SOD323-R"))
    )
    (comp (ref "DCM11")
      (value "7.5")
      (footprint "eagle-import:SOD323-R")
      (libsource (lib "eagle-import") (part "DIODE-SOD323-R"))
    )
    (comp (ref "DCM12")
      (value "7.5")
      (footprint "eagle-import:SOD323-R")
      (libsource (lib "eagle-import") (part "DIODE-SOD323-R"))
    )
    (comp (ref "DCM13")
      (value "7.5")
      (footprint "eagle-import:SOD323-R")
      (libsource (lib "eagle-import") (part "DIODE-SOD323-R"))
    )
    (comp (ref "DCM14")
      (value "7.5")
      (footprint "eagle-import:SOD323-R")
      (libsource (lib "eagle-import") (part "DIODE-SOD323-R"))
    )
    (comp (ref "DCM15")
      (value "7.5")
      (footprint "eagle-import:SOD323-R")
      (libsource (lib "eagle-import") (part "DIODE-SOD323-R"))
    )
    (comp (ref "DCM16")
      (value "7.5")
      (footprint "eagle-import:SOD323-R")
      (libsource (lib "eagle-import") (part "DIODE-SOD323-R"))
    )
    (comp (ref "QB1")
      (value "BSS84AKT")
      (footprint "eagle-import:SOT416")
      (libsource (lib "eagle-import") (part "BSS84AKT"))
    )
    (comp (ref "QB2")
      (value "BSS84AKT")
      (footprint "eagle-import:SOT416")
      (libsource (lib "eagle-import") (part "BSS84AKT"))
    )
    (comp (ref "QB3")
      (value "BSS84AKT")
      (footprint "eagle-import:SOT416")
      (libsource (lib "eagle-import") (part "BSS84AKT"))
    )
    (comp (ref "QB4")
      (value "BSS84AKT")
      (footprint "eagle-import:SOT416")
      (libsource (lib "eagle-import") (part "BSS84AKT"))
    )
    (comp (ref "QB5")
      (value "BSS84AKT")
      (footprint "eagle-import:SOT416")
      (libsource (lib "eagle-import") (part "BSS84AKT"))
    )
    (comp (ref "QB6")
      (value "BSS84AKT")
      (footprint "eagle-import:SOT416")
      (libsource (lib "eagle-import") (part "BSS84AKT"))
    )
    (comp (ref "QB7")
      (value "BSS84AKT")
      (footprint "eagle-import:SOT416")
      (libsource (lib "eagle-import") (part "BSS84AKT"))
    )
    (comp (ref "QB8")
      (value "BSS84AKT")
      (footprint "eagle-import:SOT416")
      (libsource (lib "eagle-import") (part "BSS84AKT"))
    )
    (comp (ref "QB9")
      (value "BSS84AKT")
      (footprint "eagle-import:SOT416")
      (libsource (lib "eagle-import") (part "BSS84AKT"))
    )
    (comp (ref "QB10")
      (value "BSS84AKT")
      (footprint "eagle-import:SOT416")
      (libsource (lib "eagle-import") (part "BSS84AKT"))
    )
    (comp (ref "QB11")
      (value "BSS84AKT")
      (footprint "eagle-import:SOT416")
      (libsource (lib "eagle-import") (part "BSS84AKT"))
    )
    (comp (ref "QB12")
      (value "BSS84AKT")
      (footprint "eagle-import:SOT416")
      (libsource (lib "eagle-import") (part "BSS84AKT"))
    )
    (comp (ref "QB13")
      (value "BSS84AKT")
      (footprint "eagle-import:SOT416")
      (libsource (lib "eagle-import") (part "BSS84AKT"))
    )
    (comp (ref "QB14")
      (value "BSS84AKT")
      (footprint "eagle-import:SOT416")
      (libsource (lib "eagle-import") (part "BSS84AKT"))
    )
    (comp (ref "QB15")
      (value "BSS84AKT")
      (footprint "eagle-import:SOT416")
      (libsource (lib "eagle-import") (part "BSS84AKT"))
    )
    (comp (ref "QB16")
      (value "BSS84AKT")
      (footprint "eagle-import:SOT416")
      (libsource (lib "eagle-import") (part "BSS84AKT"))
    )
    (comp (ref "RBG1")
      (value "3.3k")
      (footprint "eagle-import:R0402")
      (libsource (lib "eagle-import") (part "R0402"))
    )
    (comp (ref "RBG2")
      (value "3.3k")
      (footprint "eagle-import:R0402")
      (libsource (lib "eagle-import") (part "R0402"))
    )
    (comp (ref "RBG3")
      (value "3.3k")
      (footprint "eagle-import:R0402")
      (libsource (lib "eagle-import") (part "R0402"))
    )
    (comp (ref "RBG4")
      (value "3.3k")
      (footprint "eagle-import:R0402")
      (libsource (lib "eagle-import") (part "R0402"))
    )
    (comp (ref "RBG5")
      (value "3.3k")
      (footprint "eagle-import:R0402")
      (libsource (lib "eagle-import") (part "R0402"))
    )
    (comp (ref "RBG6")
      (value "3.3k")
      (footprint "eagle-import:R0402")
      (libsource (lib "eagle-import") (part "R0402"))
    )
    (comp (ref "RBG7")
      (value "3.3k")
      (footprint "eagle-import:R0402")
      (libsource (lib "eagle-import") (part "R0402"))
    )
    (comp (ref "RBG8")
      (value "3.3k")
      (footprint "eagle-import:R0402")
      (libsource (lib "eagle-import") (part "R0402"))
    )
    (comp (ref "RBG9")
      (value "3.3k")
      (footprint "eagle-import:R0402")
      (libsource (lib "eagle-import") (part "R0402"))
    )
    (comp (ref "RBG10")
      (value "3.3k")
      (footprint "eagle-import:R0402")
      (libsource (lib "eagle-import") (part "R0402"))
    )
    (comp (ref "RBG11")
      (value "3.3k")
      (footprint "eagle-import:R0402")
      (libsource (lib "eagle-import") (part "R0402"))
    )
    (comp (ref "RBG12")
      (value "3.3k")
      (footprint "eagle-import:R0402")
      (libsource (lib "eagle-import") (part "R0402"))
    )
    (comp (ref "RBG13")
      (value "3.3k")
      (footprint "eagle-import:R0402")
      (libsource (lib "eagle-import") (part "R0402"))
    )
    (comp (ref "RBG14")
      (value "3.3k")
      (footprint "eagle-import:R0402")
      (libsource (lib "eagle-import") (part "R0402"))
    )
    (comp (ref "RBG15")
      (value "3.3k")
      (footprint "eagle-import:R0402")
      (libsource (lib "eagle-import") (part "R0402"))
    )
    (comp (ref "RBG16")
      (value "3.3k")
      (footprint "eagle-import:R0402")
      (libsource (lib "eagle-import") (part "R0402"))
    )
    (comp (ref "RCM1")
      (value "100")
      (footprint "eagle-import:R0402")
      (libsource (lib "eagle-import") (part "R0402"))
    )
    (comp (ref "RCM2")
      (value "100")
      (footprint "eagle-import:R0402")
      (libsource (lib "eagle-import") (part "R0402"))
    )
    (comp (ref "RCM3")
      (value "100")
      (footprint "eagle-import:R0402")
      (libsource (lib "eagle-import") (part "R0402"))
    )
    (comp (ref "RCM4")
      (value "100")
      (footprint "eagle-import:R0402")
      (libsource (lib "eagle-import") (part "R0402"))
    )
    (comp (ref "RCM5")
      (value "100")
      (footprint "eagle-import:R0402")
      (libsource (lib "eagle-import") (part "R0402"))
    )
    (comp (ref "RCM6")
      (value "100")
      (footprint "eagle-import:R0402")
      (libsource (lib "eagle-import") (part "R0402"))
    )
    (comp (ref "RCM7")
      (value "100")
      (footprint "eagle-import:R0402")
      (libsource (lib "eagle-import") (part "R0402"))
    )
    (comp (ref "RCM8")
      (value "100")
      (footprint "eagle-import:R0402")
      (libsource (lib "eagle-import") (part "R0402"))
    )
    (comp (ref "RCM9")
      (value "100")
      (footprint "eagle-import:R0402")
      (libsource (lib "eagle-import") (part "R0402"))
    )
    (comp (ref "RCM10")
      (value "100")
      (footprint "eagle-import:R0402")
      (libsource (lib "eagle-import") (part "R0402"))
    )
    (comp (ref "RCM11")
      (value "100")
      (footprint "eagle-import:R0402")
      (libsource (lib "eagle-import") (part "R0402"))
    )
    (comp (ref "RCM12")
      (value "100")
      (footprint "eagle-import:R0402")
      (libsource (lib "eagle-import") (part "R0402"))
    )
    (comp (ref "RCM13")
      (value "100")
      (footprint "eagle-import:R0402")
      (libsource (lib "eagle-import") (part "R0402"))
    )
    (comp (ref "RCM14")
      (value "100")
      (footprint "eagle-import:R0402")
      (libsource (lib "eagle-import") (part "R0402"))
    )
    (comp (ref "RCM15")
      (value "100")
      (footprint "eagle-import:R0402")
      (libsource (lib "eagle-import") (part "R0402"))
    )
    (comp (ref "RCM16")
      (value "100")
      (footprint "eagle-import:R0402")
      (libsource (lib "eagle-import") (part "R0402"))
    )
    (comp (ref "RP1")
      (value "100")
      (footprint "eagle-import:R2512")
      (libsource (lib "eagle-import") (part "R2512"))
    )
    (comp (ref "RP2")
      (value "100")
      (footprint "eagle-import:R2512")
      (libsource (lib "eagle-import") (part "R2512"))
    )
    (comp (ref "RP3")
      (value "100")
      (footprint "eagle-import:R2512")
      (libsource (lib "eagle-import") (part "R2512"))
    )
    (comp (ref "RP4")
      (value "100")
      (footprint "eagle-import:R2512")
      (libsource (lib "eagle-import") (part "R2512"))
    )
    (comp (ref "RP5")
      (value "100")
      (footprint "eagle-import:R2512")
      (libsource (lib "eagle-import") (part "R2512"))
    )
    (comp (ref "RP6")
      (value "100")
      (footprint "eagle-import:R2512")
      (libsource (lib "eagle-import") (part "R2512"))
    )
    (comp (ref "RP7")
      (value "100")
      (footprint "eagle-import:R2512")
      (libsource (lib "eagle-import") (part "R2512"))
    )
    (comp (ref "RP8")
      (value "100")
      (footprint "eagle-import:R2512")
      (libsource (lib "eagle-import") (part "R2512"))
    )
    (comp (ref "RP9")
      (value "100")
      (footprint "eagle-import:R2512")
      (libsource (lib "eagle-import") (part "R2512"))
    )
    (comp (ref "RP10")
      (value "100")
      (footprint "eagle-import:R2512")
      (libsource (lib "eagle-import") (part "R2512"))
    )
    (comp (ref "RP11")
      (value "100")
      (footprint "eagle-import:R2512")
      (libsource (lib "eagle-import") (part "R2512"))
    )
    (comp (ref "RP12")
      (value "100")
      (footprint "eagle-import:R2512")
      (libsource (lib "eagle-import") (part "R2512"))
    )
    (comp (ref "RP13")
      (value "100")
      (footprint "eagle-import:R2512")
      (libsource (lib "eagle-import") (part "R2512"))
    )
    (comp (ref "RP14")
      (value "100")
      (footprint "eagle-import:R2512")
      (libsource (lib "eagle-import") (part "R2512"))
    )
    (comp (ref "RP15")
      (value "100")
      (footprint "eagle-import:R2512")
      (libsource (lib "eagle-import") (part "R2512"))
    )
    (comp (ref "RP16")
      (value "100")
      (footprint "eagle-import:R2512")
      (libsource (lib "eagle-import") (part "R2512"))
    )
  )
  (nets
    (net (code "1") (name "BAL1") (class "Default")
      (node (ref "IC2") (pin "25") (pinfunction "S1_25") (pintype "bidirectional"))
      (node (ref "RBG1") (pin "2") (pinfunction "2_2") (pintype "passive"))
    )
    (net (code "2") (name "BAL2") (class "Default")
      (node (ref "IC2") (pin "23") (pinfunction "S2_23") (pintype "bidirectional"))
      (node (ref "RBG2") (pin "2") (pinfunction "2_2") (pintype "passive"))
    )
    (net (code "3") (name "BAL3") (class "Default")
      (node (ref "IC2") (pin "21") (pinfunction "S3_21") (pintype "bidirectional"))
      (node (ref "RBG3") (pin "2") (pinfunction "2_2") (pintype "passive"))
    )
    (net (code "4") (name "BAL4") (class "Default")
      (node (ref "IC2") (pin "19") (pinfunction "S4_19") (pintype "bidirectional"))
      (node (ref "RBG4") (pin "2") (pinfunction "2_2") (pintype "passive"))
    )
    (net (code "5") (name "BAL5") (class "Default")
      (node (ref "IC2") (pin "17") (pinfunction "S5_17") (pintype "bidirectional"))
      (node (ref "RBG5") (pin "2") (pinfunction "2_2") (pintype "passive"))
    )
    (net (code "6") (name "BAL6") (class "Default")
      (node (ref "IC2") (pin "15") (pinfunction "S6_15") (pintype "bidirectional"))
      (node (ref "RBG6") (pin "2") (pinfunction "2_2") (pintype "passive"))
    )
    (net (code "7") (name "BAL7") (class "Default")
      (node (ref "IC2") (pin "13") (pinfunction "S7_13") (pintype "bidirectional"))
      (node (ref "RBG7") (pin "2") (pinfunction "2_2") (pintype "passive"))
    )
    (net (code "8") (name "BAL8") (class "Default")
      (node (ref "IC2") (pin "11") (pinfunction "S8_11") (pintype "bidirectional"))
      (node (ref "RBG8") (pin "2") (pinfunction "2_2") (pintype "passive"))
    )
    (net (code "9") (name "BAL9") (class "Default")
      (node (ref "IC8") (pin "25") (pinfunction "S1_25") (pintype "bidirectional"))
      (node (ref "RBG9") (pin "2") (pinfunction "2_2") (pintype "passive"))
    )
    (net (code "10") (name "BAL10") (class "Default")
      (node (ref "IC8") (pin "23") (pinfunction "S2_23") (pintype "bidirectional"))
      (node (ref "RBG10") (pin "2") (pinfunction "2_2") (pintype "passive"))
    )
    (net (code "11") (name "BAL11") (class "Default")
      (node (ref "IC8") (pin "21") (pinfunction "S3_21") (pintype "bidirectional"))
      (node (ref "RBG11") (pin "2") (pinfunction "2_2") (pintype "passive"))
    )
    (net (code "12") (name "BAL12") (class "Default")
      (node (ref "IC8") (pin "19") (pinfunction "S4_19") (pintype "bidirectional"))
      (node (ref "RBG12") (pin "2") (pinfunction "2_2") (pintype "passive"))
    )
    (net (code "13") (name "BAL13") (class "Default")
      (node (ref "IC8") (pin "17") (pinfunction "S5_17") (pintype "bidirectional"))
      (node (ref "RBG13") (pin "2") (pinfunction "2_2") (pintype "passive"))
    )
    (net (code "14") (name "BAL14") (class "Default")
      (node (ref "IC8") (pin "15") (pinfunction "S6_15") (pintype "bidirectional"))
      (node (ref "RBG14") (pin "2") (pinfunction "2_2") (pintype "passive"))
    )
    (net (code "15") (name "BAL15") (class "Default")
      (node (ref "IC8") (pin "13") (pinfunction "S7_13") (pintype "bidirectional"))
      (node (ref "RBG15") (pin "2") (pinfunction "2_2") (pintype "passive"))
    )
    (net (code "16") (name "BAL16") (class "Default")
      (node (ref "IC8") (pin "11") (pinfunction "S8_11") (pintype "bidirectional"))
      (node (ref "RBG16") (pin "2") (pinfunction "2_2") (pintype "passive"))
    )
    (net (code "17") (name "C0") (class "Default")
      (node (ref "CCM1") (pin "2") (pinfunction "2_2") (pintype "passive"))
      (node (ref "DCM1") (pin "A") (pinfunction "A_A") (pintype "passive"))
      (node (ref "IC2") (pin "26") (pinfunction "C0_26") (pintype "bidirectional"))
      (node (ref "L_V-R") (pin "1") (pinfunction "1_1") (pintype "passive"))
      (node (ref "RP1") (pin "1") (pinfunction "1_1") (pintype "passive"))
      (node (ref "X1") (pin "8") (pinfunction "S_8") (pintype "passive"))
    )
    (net (code "18") (name "C1") (class "Default")
      (node (ref "QB1") (pin "2") (pinfunction "S_2") (pintype "passive"))
      (node (ref "RCM1") (pin "1") (pinfunction "1_1") (pintype "passive"))
      (node (ref "RP2") (pin "1") (pinfunction "1_1") (pintype "passive"))
      (node (ref "X1") (pin "7") (pinfunction "S_7") (pintype "passive"))
    )
    (net (code "19") (name "C1M") (class "Default")
      (node (ref "CCM1") (pin "1") (pinfunction "1_1") (pintype "passive"))
      (node (ref "CCM2") (pin "2") (pinfunction "2_2") (pintype "passive"))
      (node (ref "DCM1") (pin "C") (pinfunction "C_C") (pintype "passive"))
      (node (ref "DCM2") (pin "A") (pinfunction "A_A") (pintype "passive"))
      (node (ref "IC2") (pin "24") (pinfunction "C1_24") (pintype "bidirectional"))
      (node (ref "RCM1") (pin "2") (pinfunction "2_2") (pintype "passive"))
    )
    (net (code "20") (name "C2") (class "Default")
      (node (ref "QB2") (pin "2") (pinfunction "S_2") (pintype "passive"))
      (node (ref "RCM2") (pin "1") (pinfunction "1_1") (pintype "passive"))
      (node (ref "RP3") (pin "1") (pinfunction "1_1") (pintype "passive"))
      (node (ref "X1") (pin "6") (pinfunction "S_6") (pintype "passive"))
    )
    (net (code "21") (name "C2M") (class "Default")
      (node (ref "CCM2") (pin "1") (pinfunction "1_1") (pintype "passive"))
      (node (ref "CCM3") (pin "2") (pinfunction "2_2") (pintype "passive"))
      (node (ref "DCM2") (pin "C") (pinfunction "C_C") (pintype "passive"))
      (node (ref "DCM3") (pin "A") (pinfunction "A_A") (pintype "passive"))
      (node (ref "IC2") (pin "22") (pinfunction "C2_22") (pintype "bidirectional"))
      (node (ref "RCM2") (pin "2") (pinfunction "2_2") (pintype "passive"))
    )
    (net (code "22") (name "C3") (class "Default")
      (node (ref "QB3") (pin "2") (pinfunction "S_2") (pintype "passive"))
      (node (ref "RCM3") (pin "1") (pinfunction "1_1") (pintype "passive"))
      (node (ref "RP4") (pin "1") (pinfunction "1_1") (pintype "passive"))
      (node (ref "X1") (pin "5") (pinfunction "S_5") (pintype "passive"))
    )
    (net (code "23") (name "C3M") (class "Default")
      (node (ref "CCM3") (pin "1") (pinfunction "1_1") (pintype "passive"))
      (node (ref "CCM4") (pin "2") (pinfunction "2_2") (pintype "passive"))
      (node (ref "DCM3") (pin "C") (pinfunction "C_C") (pintype "passive"))
      (node (ref "DCM4") (pin "A") (pinfunction "A_A") (pintype "passive"))
      (node (ref "IC2") (pin "20") (pinfunction "C3_20") (pintype "bidirectional"))
      (node (ref "RCM3") (pin "2") (pinfunction "2_2") (pintype "passive"))
    )
    (net (code "24") (name "C4") (class "Default")
      (node (ref "QB4") (pin "2") (pinfunction "S_2") (pintype "passive"))
      (node (ref "RCM4") (pin "1") (pinfunction "1_1") (pintype "passive"))
      (node (ref "RP5") (pin "1") (pinfunction "1_1") (pintype "passive"))
      (node (ref "X1") (pin "4") (pinfunction "S_4") (pintype "passive"))
    )
    (net (code "25") (name "C4M") (class "Default")
      (node (ref "CCM4") (pin "1") (pinfunction "1_1") (pintype "passive"))
      (node (ref "CCM5") (pin "2") (pinfunction "2_2") (pintype "passive"))
      (node (ref "DCM4") (pin "C") (pinfunction "C_C") (pintype "passive"))
      (node (ref "DCM5") (pin "A") (pinfunction "A_A") (pintype "passive"))
      (node (ref "IC2") (pin "18") (pinfunction "C4_18") (pintype "bidirectional"))
      (node (ref "RCM4") (pin "2") (pinfunction "2_2") (pintype "passive"))
    )
    (net (code "26") (name "C5") (class "Default")
      (node (ref "QB5") (pin "2") (pinfunction "S_2") (pintype "passive"))
      (node (ref "RCM5") (pin "1") (pinfunction "1_1") (pintype "passive"))
      (node (ref "RP6") (pin "1") (pinfunction "1_1") (pintype "passive"))
      (node (ref "X1") (pin "3") (pinfunction "S_3") (pintype "passive"))
    )
    (net (code "27") (name "C5M") (class "Default")
      (node (ref "CCM5") (pin "1") (pinfunction "1_1") (pintype "passive"))
      (node (ref "CCM6") (pin "2") (pinfunction "2_2") (pintype "passive"))
      (node (ref "DCM5") (pin "C") (pinfunction "C_C") (pintype "passive"))
      (node (ref "DCM6") (pin "A") (pinfunction "A_A") (pintype "passive"))
      (node (ref "IC2") (pin "16") (pinfunction "C5_16") (pintype "bidirectional"))
      (node (ref "RCM5") (pin "2") (pinfunction "2_2") (pintype "passive"))
    )
    (net (code "28") (name "C6") (class "Default")
      (node (ref "QB6") (pin "2") (pinfunction "S_2") (pintype "passive"))
      (node (ref "RCM6") (pin "1") (pinfunction "1_1") (pintype "passive"))
      (node (ref "RP7") (pin "1") (pinfunction "1_1") (pintype "passive"))
      (node (ref "X1") (pin "2") (pinfunction "S_2") (pintype "passive"))
    )
    (net (code "29") (name "C6M") (class "Default")
      (node (ref "CCM6") (pin "1") (pinfunction "1_1") (pintype "passive"))
      (node (ref "CCM7") (pin "2") (pinfunction "2_2") (pintype "passive"))
      (node (ref "DCM6") (pin "C") (pinfunction "C_C") (pintype "passive"))
      (node (ref "DCM7") (pin "A") (pinfunction "A_A") (pintype "passive"))
      (node (ref "IC2") (pin "14") (pinfunction "C6_14") (pintype "bidirectional"))
      (node (ref "RCM6") (pin "2") (pinfunction "2_2") (pintype "passive"))
    )
    (net (code "30") (name "C7") (class "Default")
      (node (ref "QB7") (pin "2") (pinfunction "S_2") (pintype "passive"))
      (node (ref "RCM7") (pin "1") (pinfunction "1_1") (pintype "passive"))
      (node (ref "RP8") (pin "1") (pinfunction "1_1") (pintype "passive"))
      (node (ref "X1") (pin "1") (pinfunction "S_1") (pintype "passive"))
    )
    (net (code "31") (name "C7M") (class "Default")
      (node (ref "CCM7") (pin "1") (pinfunction "1_1") (pintype "passive"))
      (node (ref "CCM8") (pin "2") (pinfunction "2_2") (pintype "passive"))
      (node (ref "DCM7") (pin "C") (pinfunction "C_C") (pintype "passive"))
      (node (ref "DCM8") (pin "A") (pinfunction "A_A") (pintype "passive"))
      (node (ref "IC2") (pin "12") (pinfunction "C7_12") (pintype "bidirectional"))
      (node (ref "RCM7") (pin "2") (pinfunction "2_2") (pintype "passive"))
    )
    (net (code "32") (name "C8") (class "Default")
      (node (ref "CCM9") (pin "2") (pinfunction "2_2") (pintype "passive"))
      (node (ref "DCM9") (pin "A") (pinfunction "A_A") (pintype "passive"))
      (node (ref "H_V-R") (pin "1") (pinfunction "1_1") (pintype "passive"))
      (node (ref "IC8") (pin "26") (pinfunction "C0_26") (pintype "bidirectional"))
      (node (ref "L7") (pin "1") (pinfunction "1_1") (pintype "passive"))
      (node (ref "QB8") (pin "2") (pinfunction "S_2") (pintype "passive"))
      (node (ref "RCM8") (pin "1") (pinfunction "1_1") (pintype "passive"))
      (node (ref "RP9") (pin "1") (pinfunction "1_1") (pintype "passive"))
      (node (ref "X4") (pin "9") (pinfunction "S_9") (pintype "passive"))
    )
    (net (code "33") (name "C8M") (class "Default")
      (node (ref "CCM8") (pin "1") (pinfunction "1_1") (pintype "passive"))
      (node (ref "DCM8") (pin "C") (pinfunction "C_C") (pintype "passive"))
      (node (ref "IC2") (pin "10") (pinfunction "C8_10") (pintype "bidirectional"))
      (node (ref "IC2") (pin "2") (pinfunction "C12_2") (pintype "bidirectional"))
      (node (ref "IC2") (pin "4") (pinfunction "C11_4") (pintype "bidirectional"))
      (node (ref "IC2") (pin "6") (pinfunction "C10_6") (pintype "bidirectional"))
      (node (ref "IC2") (pin "8") (pinfunction "C9_8") (pintype "bidirectional"))
      (node (ref "RCM8") (pin "2") (pinfunction "2_2") (pintype "passive"))
    )
    (net (code "34") (name "C9") (class "Default")
      (node (ref "QB9") (pin "2") (pinfunction "S_2") (pintype "passive"))
      (node (ref "RCM9") (pin "1") (pinfunction "1_1") (pintype "passive"))
      (node (ref "RP10") (pin "1") (pinfunction "1_1") (pintype "passive"))
      (node (ref "X4") (pin "8") (pinfunction "S_8") (pintype "passive"))
    )
    (net (code "35") (name "C9M") (class "Default")
      (node (ref "CCM10") (pin "2") (pinfunction "2_2") (pintype "passive"))
      (node (ref "CCM9") (pin "1") (pinfunction "1_1") (pintype "passive"))
      (node (ref "DCM10") (pin "A") (pinfunction "A_A") (pintype "passive"))
      (node (ref "DCM9") (pin "C") (pinfunction "C_C") (pintype "passive"))
      (node (ref "IC8") (pin "24") (pinfunction "C1_24") (pintype "bidirectional"))
      (node (ref "RCM9") (pin "2") (pinfunction "2_2") (pintype "passive"))
    )
    (net (code "36") (name "C10") (class "Default")
      (node (ref "QB10") (pin "2") (pinfunction "S_2") (pintype "passive"))
      (node (ref "RCM10") (pin "1") (pinfunction "1_1") (pintype "passive"))
      (node (ref "RP11") (pin "1") (pinfunction "1_1") (pintype "passive"))
      (node (ref "X4") (pin "7") (pinfunction "S_7") (pintype "passive"))
    )
    (net (code "37") (name "C10M") (class "Default")
      (node (ref "CCM10") (pin "1") (pinfunction "1_1") (pintype "passive"))
      (node (ref "CCM11") (pin "2") (pinfunction "2_2") (pintype "passive"))
      (node (ref "DCM10") (pin "C") (pinfunction "C_C") (pintype "passive"))
      (node (ref "DCM11") (pin "A") (pinfunction "A_A") (pintype "passive"))
      (node (ref "IC8") (pin "22") (pinfunction "C2_22") (pintype "bidirectional"))
      (node (ref "RCM10") (pin "2") (pinfunction "2_2") (pintype "passive"))
    )
    (net (code "38") (name "C11") (class "Default")
      (node (ref "QB11") (pin "2") (pinfunction "S_2") (pintype "passive"))
      (node (ref "RCM11") (pin "1") (pinfunction "1_1") (pintype "passive"))
      (node (ref "RP12") (pin "1") (pinfunction "1_1") (pintype "passive"))
      (node (ref "X4") (pin "6") (pinfunction "S_6") (pintype "passive"))
    )
    (net (code "39") (name "C11M") (class "Default")
      (node (ref "CCM11") (pin "1") (pinfunction "1_1") (pintype "passive"))
      (node (ref "CCM12") (pin "2") (pinfunction "2_2") (pintype "passive"))
      (node (ref "DCM11") (pin "C") (pinfunction "C_C") (pintype "passive"))
      (node (ref "DCM12") (pin "A") (pinfunction "A_A") (pintype "passive"))
      (node (ref "IC8") (pin "20") (pinfunction "C3_20") (pintype "bidirectional"))
      (node (ref "RCM11") (pin "2") (pinfunction "2_2") (pintype "passive"))
    )
    (net (code "40") (name "C12") (class "Default")
      (node (ref "QB12") (pin "2") (pinfunction "S_2") (pintype "passive"))
      (node (ref "RCM12") (pin "1") (pinfunction "1_1") (pintype "passive"))
      (node (ref "RP13") (pin "1") (pinfunction "1_1") (pintype "passive"))
      (node (ref "X4") (pin "5") (pinfunction "S_5") (pintype "passive"))
    )
    (net (code "41") (name "C12M") (class "Default")
      (node (ref "CCM12") (pin "1") (pinfunction "1_1") (pintype "passive"))
      (node (ref "CCM13") (pin "2") (pinfunction "2_2") (pintype "passive"))
      (node (ref "DCM12") (pin "C") (pinfunction "C_C") (pintype "passive"))
      (node (ref "DCM13") (pin "A") (pinfunction "A_A") (pintype "passive"))
      (node (ref "IC8") (pin "18") (pinfunction "C4_18") (pintype "bidirectional"))
      (node (ref "RCM12") (pin "2") (pinfunction "2_2") (pintype "passive"))
    )
    (net (code "42") (name "C13") (class "Default")
      (node (ref "QB13") (pin "2") (pinfunction "S_2") (pintype "passive"))
      (node (ref "RCM13") (pin "1") (pinfunction "1_1") (pintype "passive"))
      (node (ref "RP14") (pin "1") (pinfunction "1_1") (pintype "passive"))
      (node (ref "X4") (pin "4") (pinfunction "S_4") (pintype "passive"))
    )
    (net (code "43") (name "C13M") (class "Default")
      (node (ref "CCM13") (pin "1") (pinfunction "1_1") (pintype "passive"))
      (node (ref "CCM14") (pin "2") (pinfunction "2_2") (pintype "passive"))
      (node (ref "DCM13") (pin "C") (pinfunction "C_C") (pintype "passive"))
      (node (ref "DCM14") (pin "A") (pinfunction "A_A") (pintype "passive"))
      (node (ref "IC8") (pin "16") (pinfunction "C5_16") (pintype "bidirectional"))
      (node (ref "RCM13") (pin "2") (pinfunction "2_2") (pintype "passive"))
    )
    (net (code "44") (name "C14") (class "Default")
      (node (ref "QB14") (pin "2") (pinfunction "S_2") (pintype "passive"))
      (node (ref "RCM14") (pin "1") (pinfunction "1_1") (pintype "passive"))
      (node (ref "RP15") (pin "1") (pinfunction "1_1") (pintype "passive"))
      (node (ref "X4") (pin "3") (pinfunction "S_3") (pintype "passive"))
    )
    (net (code "45") (name "C14M") (class "Default")
      (node (ref "CCM14") (pin "1") (pinfunction "1_1") (pintype "passive"))
      (node (ref "CCM15") (pin "2") (pinfunction "2_2") (pintype "passive"))
      (node (ref "DCM14") (pin "C") (pinfunction "C_C") (pintype "passive"))
      (node (ref "DCM15") (pin "A") (pinfunction "A_A") (pintype "passive"))
      (node (ref "IC8") (pin "14") (pinfunction "C6_14") (pintype "bidirectional"))
      (node (ref "RCM14") (pin "2") (pinfunction "2_2") (pintype "passive"))
    )
    (net (code "46") (name "C15") (class "Default")
      (node (ref "QB15") (pin "2") (pinfunction "S_2") (pintype "passive"))
      (node (ref "RCM15") (pin "1") (pinfunction "1_1") (pintype "passive"))
      (node (ref "RP16") (pin "1") (pinfunction "1_1") (pintype "passive"))
      (node (ref "X4") (pin "2") (pinfunction "S_2") (pintype "passive"))
    )
    (net (code "47") (name "C15M") (class "Default")
      (node (ref "CCM15") (pin "1") (pinfunction "1_1") (pintype "passive"))
      (node (ref "CCM16") (pin "2") (pinfunction "2_2") (pintype "passive"))
      (node (ref "DCM15") (pin "C") (pinfunction "C_C") (pintype "passive"))
      (node (ref "DCM16") (pin "A") (pinfunction "A_A") (pintype "passive"))
      (node (ref "IC8") (pin "12") (pinfunction "C7_12") (pintype "bidirectional"))
      (node (ref "RCM15") (pin "2") (pinfunction "2_2") (pintype "passive"))
    )
    (net (code "48") (name "C16") (class "Default")
      (node (ref "L5") (pin "1") (pinfunction "1_1") (pintype "passive"))
      (node (ref "QB16") (pin "2") (pinfunction "S_2") (pintype "passive"))
      (node (ref "RCM16") (pin "1") (pinfunction "1_1") (pintype "passive"))
      (node (ref "X4") (pin "1") (pinfunction "S_1") (pintype "passive"))
    )
    (net (code "49") (name "C16M") (class "Default")
      (node (ref "CCM16") (pin "1") (pinfunction "1_1") (pintype "passive"))
      (node (ref "DCM16") (pin "C") (pinfunction "C_C") (pintype "passive"))
      (node (ref "IC8") (pin "10") (pinfunction "C8_10") (pintype "bidirectional"))
      (node (ref "IC8") (pin "2") (pinfunction "C12_2") (pintype "bidirectional"))
      (node (ref "IC8") (pin "4") (pinfunction "C11_4") (pintype "bidirectional"))
      (node (ref "IC8") (pin "6") (pinfunction "C10_6") (pintype "bidirectional"))
      (node (ref "IC8") (pin "8") (pinfunction "C9_8") (pintype "bidirectional"))
      (node (ref "RCM16") (pin "2") (pinfunction "2_2") (pintype "passive"))
    )
    (net (code "50") (name "CANH") (class "Default")
      (node (ref "D6") (pin "1") (pinfunction "1_1") (pintype "passive"))
      (node (ref "D9") (pin "2") (pinfunction "2_2") (pintype "passive"))
      (node (ref "L11") (pin "1") (pinfunction "1_1") (pintype "passive"))
      (node (ref "L8") (pin "1") (pinfunction "1_1") (pintype "passive"))
      (node (ref "SJ1") (pin "2") (pinfunction "2_2") (pintype "passive"))
      (node (ref "X3") (pin "3") (pinfunction "S_3") (pintype "passive"))
      (node (ref "X6") (pin "3") (pinfunction "S_3") (pintype "passive"))
    )
    (net (code "51") (name "CANL") (class "Default")
      (node (ref "D5") (pin "1") (pinfunction "1_1") (pintype "passive"))
      (node (ref "D8") (pin "2") (pinfunction "2_2") (pintype "passive"))
      (node (ref "L11") (pin "3") (pinfunction "3_3") (pintype "passive"))
      (node (ref "L8") (pin "3") (pinfunction "3_3") (pintype "passive"))
      (node (ref "R22") (pin "2") (pinfunction "2_2") (pintype "passive"))
      (node (ref "X3") (pin "4") (pinfunction "S_4") (pintype "passive"))
      (node (ref "X6") (pin "4") (pinfunction "S_4") (pintype "passive"))
    )
    (net (code "52") (name "CAR+12V") (class "Default")
      (node (ref "C3") (pin "1") (pinfunction "1_1") (pintype "passive"))
      (node (ref "DCIN") (pin "1") (pinfunction "VI_1") (pintype "bidirectional"))
      (node (ref "L1") (pin "1") (pinfunction "1_1") (pintype "passive"))
    )
    (net (code "53") (name "CAR+12VIN") (class "Default")
      (node (ref "C2") (pin "1") (pinfunction "1_1") (pintype "passive"))
      (node (ref "D10") (pin "2") (pinfunction "2_2") (pintype "passive"))
      (node (ref "D7") (pin "1") (pinfunction "1_1") (pintype "passive"))
      (node (ref "L1") (pin "2") (pinfunction "2_2") (pintype "passive"))
      (node (ref "X3") (pin "1") (pinfunction "S_1") (pintype "passive"))
      (node (ref "X3") (pin "2") (pinfunction "S_2") (pintype "passive"))
      (node (ref "X6") (pin "1") (pinfunction "S_1") (pintype "passive"))
      (node (ref "X6") (pin "2") (pinfunction "S_2") (pintype "passive"))
    )
    (net (code "54") (name "CARGND") (class "Default")
      (node (ref "C16") (pin "2") (pinfunction "2_2") (pintype "passive"))
      (node (ref "C17") (pin "2") (pinfunction "2_2") (pintype "passive"))
      (node (ref "C18") (pin "2") (pinfunction "2_2") (pintype "passive"))
      (node (ref "C2") (pin "2") (pinfunction "2_2") (pintype "passive"))
      (node (ref "C20") (pin "2") (pinfunction "2_2") (pintype "passive"))
      (node (ref "C26") (pin "2") (pinfunction "2_2") (pintype "passive"))
      (node (ref "C3") (pin "2") (pinfunction "2_2") (pintype "passive"))
      (node (ref "C6") (pin "2") (pinfunction "2_2") (pintype "passive"))
      (node (ref "C7") (pin "2") (pinfunction "2_2") (pintype "passive"))
      (node (ref "D10") (pin "1") (pinfunction "1_1") (pintype "passive"))
      (node (ref "D5") (pin "2") (pinfunction "2_2") (pintype "passive"))
      (node (ref "D6") (pin "2") (pinfunction "2_2") (pintype "passive"))
      (node (ref "D7") (pin "2") (pinfunction "2_2") (pintype "passive"))
      (node (ref "D8") (pin "1") (pinfunction "1_1") (pintype "passive"))
      (node (ref "D9") (pin "1") (pinfunction "1_1") (pintype "passive"))
      (node (ref "DCDC1") (pin "1") (pinfunction "VIN-_1") (pintype "bidirectional"))
      (node (ref "DCDC2") (pin "1") (pinfunction "VIN-_1") (pintype "bidirectional"))
      (node (ref "DCIN") (pin "2") (pinfunction "GND_2") (pintype "bidirectional"))
      (node (ref "IC3") (pin "4") (pinfunction "GND1_4") (pintype "bidirectional"))
      (node (ref "IC4") (pin "2") (pinfunction "VSS_2") (pintype "bidirectional"))
      (node (ref "IC5") (pin "2") (pinfunction "VSS_2") (pintype "bidirectional"))
      (node (ref "IC6") (pin "4") (pinfunction "GND1_4") (pintype "bidirectional"))
      (node (ref "R12") (pin "2") (pinfunction "2_2") (pintype "passive"))
      (node (ref "R39") (pin "2") (pinfunction "2_2") (pintype "passive"))
      (node (ref "X3") (pin "5") (pinfunction "S_5") (pintype "passive"))
      (node (ref "X3") (pin "6") (pinfunction "S_6") (pintype "passive"))
      (node (ref "X6") (pin "5") (pinfunction "S_5") (pintype "passive"))
      (node (ref "X6") (pin "6") (pinfunction "S_6") (pintype "passive"))
    )
    (net (code "55") (name "H+3V3") (class "Default")
      (node (ref "C13") (pin "1") (pinfunction "1_1") (pintype "passive"))
      (node (ref "C32") (pin "1") (pinfunction "1_1") (pintype "passive"))
      (node (ref "C33") (pin "1") (pinfunction "1_1") (pintype "passive"))
      (node (ref "C5") (pin "1") (pinfunction "1_1") (pintype "passive"))
      (node (ref "C8") (pin "1") (pinfunction "1_1") (pintype "passive"))
      (node (ref "C9") (pin "1") (pinfunction "1_1") (pintype "passive"))
      (node (ref "IC3") (pin "8") (pinfunction "VDD2_8") (pintype "bidirectional"))
      (node (ref "IC7") (pin "44") (pinfunction "VDD_44") (pintype "bidirectional"))
      (node (ref "IC7") (pin "8") (pinfunction "VDD_8") (pintype "bidirectional"))
      (node (ref "IC8") (pin "30") (pinfunction "VTEMP2_30") (pintype "bidirectional"))
      (node (ref "JP2") (pin "2") (pinfunction "2_2") (pintype "passive"))
      (node (ref "L2") (pin "1") (pinfunction "1_1") (pintype "passive"))
      (node (ref "LED1") (pin "A") (pinfunction "A_A") (pintype "passive"))
      (node (ref "LED19") (pin "A") (pinfunction "A_A") (pintype "passive"))
      (node (ref "NTC_R1") (pin "2") (pinfunction "2_2") (pintype "passive"))
      (node (ref "NTC_R2") (pin "2") (pinfunction "2_2") (pintype "passive"))
      (node (ref "Q5") (pin "1") (pinfunction "G_1") (pintype "passive"))
      (node (ref "R25") (pin "2") (pinfunction "2_2") (pintype "passive"))
      (node (ref "R51") (pin "1") (pinfunction "1_1") (pintype "passive"))
      (node (ref "R9") (pin "1") (pinfunction "1_1") (pintype "passive"))
      (node (ref "RGQ1_6") (pin "2") (pinfunction "2_2") (pintype "passive"))
    )
    (net (code "56") (name "HGND") (class "Default")
      (node (ref "C13") (pin "2") (pinfunction "2_2") (pintype "passive"))
      (node (ref "C24") (pin "2") (pinfunction "2_2") (pintype "passive"))
      (node (ref "C25") (pin "1") (pinfunction "1_1") (pintype "passive"))
      (node (ref "C31") (pin "1") (pinfunction "1_1") (pintype "passive"))
      (node (ref "C32") (pin "2") (pinfunction "2_2") (pintype "passive"))
      (node (ref "C33") (pin "2") (pinfunction "2_2") (pintype "passive"))
      (node (ref "C35") (pin "2") (pinfunction "2_2") (pintype "passive"))
      (node (ref "C4") (pin "2") (pinfunction "2_2") (pintype "passive"))
      (node (ref "C5") (pin "2") (pinfunction "2_2") (pintype "passive"))
      (node (ref "C8") (pin "2") (pinfunction "2_2") (pintype "passive"))
      (node (ref "C9") (pin "2") (pinfunction "2_2") (pintype "passive"))
      (node (ref "CFSM1") (pin "1") (pinfunction "1_1") (pintype "passive"))
      (node (ref "CVREF1") (pin "1") (pinfunction "1_1") (pintype "passive"))
      (node (ref "CVREG1") (pin "1") (pinfunction "1_1") (pintype "passive"))
      (node (ref "D3") (pin "A") (pinfunction "A_A") (pintype "passive"))
      (node (ref "DCDC1") (pin "4") (pinfunction "VOUT-_4") (pintype "bidirectional"))
      (node (ref "H_V-R") (pin "2") (pinfunction "2_2") (pintype "passive"))
      (node (ref "IC3") (pin "5") (pinfunction "GND2_5") (pintype "bidirectional"))
      (node (ref "IC7") (pin "41") (pinfunction "VSS_41") (pintype "bidirectional"))
      (node (ref "IC7") (pin "5") (pinfunction "VSS_5") (pintype "bidirectional"))
      (node (ref "IC8") (pin "27") (pinfunction "V-_27") (pintype "bidirectional"))
      (node (ref "IC8") (pin "33") (pinfunction "TOS_33") (pintype "bidirectional"))
      (node (ref "IC8") (pin "34") (pinfunction "WDTB_34") (pintype "bidirectional"))
      (node (ref "IC8") (pin "35") (pinfunction "GPIO1_35") (pintype "bidirectional"))
      (node (ref "IC8") (pin "36") (pinfunction "GPIO2_36") (pintype "bidirectional"))
      (node (ref "IC8") (pin "37") (pinfunction "A0_37") (pintype "bidirectional"))
      (node (ref "IC8") (pin "38") (pinfunction "A1_38") (pintype "bidirectional"))
      (node (ref "IC8") (pin "39") (pinfunction "A2_39") (pintype "bidirectional"))
      (node (ref "IC8") (pin "40") (pinfunction "A3_40") (pintype "bidirectional"))
      (node (ref "JP2") (pin "6") (pinfunction "6_6") (pintype "passive"))
      (node (ref "NTC_C1") (pin "2") (pinfunction "2_2") (pintype "passive"))
      (node (ref "NTC_C2") (pin "2") (pinfunction "2_2") (pintype "passive"))
      (node (ref "Q3") (pin "2") (pinfunction "S_2") (pintype "passive"))
      (node (ref "Q5") (pin "2") (pinfunction "S_2") (pintype "passive"))
      (node (ref "R16") (pin "1") (pinfunction "1_1") (pintype "passive"))
      (node (ref "R24") (pin "1") (pinfunction "1_1") (pintype "passive"))
      (node (ref "R43") (pin "1") (pinfunction "1_1") (pintype "passive"))
      (node (ref "R50") (pin "1") (pinfunction "1_1") (pintype "passive"))
      (node (ref "RGQ1_6") (pin "1") (pinfunction "1_1") (pintype "passive"))
      (node (ref "X2") (pin "1") (pinfunction "S_1") (pintype "passive"))
      (node (ref "X2") (pin "3") (pinfunction "S_3") (pintype "passive"))
    )
    (net (code "57") (name "H_AD1") (class "Default")
      (node (ref "IC7") (pin "33") (pinfunction "PIO1_0/AD1/CT32B1_CAP0_33") (pintype "bidirectional"))
      (node (ref "NTC_C1") (pin "1") (pinfunction "1_1") (pintype "passive"))
      (node (ref "NTC_R1") (pin "1") (pinfunction "1_1") (pintype "passive"))
      (node (ref "X2") (pin "2") (pinfunction "S_2") (pintype "passive"))
    )
    (net (code "58") (name "H_AD2") (class "Default")
      (node (ref "IC7") (pin "34") (pinfunction "PIO1_1/AD2/CT32B1_MAT0_34") (pintype "bidirectional"))
      (node (ref "NTC_C2") (pin "1") (pinfunction "1_1") (pintype "passive"))
      (node (ref "NTC_R2") (pin "1") (pinfunction "1_1") (pintype "passive"))
      (node (ref "X2") (pin "4") (pinfunction "S_4") (pintype "passive"))
    )
    (net (code "59") (name "H_CANRX") (class "Default")
      (node (ref "IC3") (pin "6") (pinfunction "O2_6") (pintype "bidirectional"))
      (node (ref "R49") (pin "2") (pinfunction "2_2") (pintype "passive"))
    )
    (net (code "60") (name "H_CANTX") (class "Default")
      (node (ref "IC3") (pin "7") (pinfunction "I1_7") (pintype "bidirectional"))
      (node (ref "R48") (pin "2") (pinfunction "2_2") (pintype "passive"))
    )
    (net (code "61") (name "H_CSB") (class "Default")
      (node (ref "IC8") (pin "44") (pinfunction "CSBI_44") (pintype "bidirectional"))
      (node (ref "R44") (pin "2") (pinfunction "2_2") (pintype "passive"))
      (node (ref "R58") (pin "1") (pinfunction "1_1") (pintype "passive"))
    )
    (net (code "62") (name "H_FSM") (class "Default")
      (node (ref "CFSM1") (pin "2") (pinfunction "2_2") (pintype "passive"))
      (node (ref "IC8") (pin "29") (pinfunction "VTEMP1_29") (pintype "bidirectional"))
      (node (ref "R10") (pin "1") (pinfunction "1_1") (pintype "passive"))
      (node (ref "R16") (pin "2") (pinfunction "2_2") (pintype "passive"))
    )
    (net (code "63") (name "H_ISP_CAN") (class "Default")
      (node (ref "IC7") (pin "14") (pinfunction "PIO0_3_14") (pintype "bidirectional"))
      (node (ref "R50") (pin "2") (pinfunction "2_2") (pintype "passive"))
    )
    (net (code "64") (name "H_ISP_ENTER") (class "Default")
      (node (ref "IC7") (pin "4") (pinfunction "PIO0_1/CLKOUT/CT32B0_MAT2_4") (pintype "bidirectional"))
      (node (ref "JP2") (pin "5") (pinfunction "5_5") (pintype "passive"))
      (node (ref "R51") (pin "2") (pinfunction "2_2") (pintype "passive"))
    )
    (net (code "65") (name "H_LED") (class "Default")
      (node (ref "IC7") (pin "48") (pinfunction "PIO3_3/~{RI}_48") (pintype "bidirectional"))
      (node (ref "Q3") (pin "1") (pinfunction "G_1") (pintype "passive"))
    )
    (net (code "66") (name "H_SCK") (class "Default")
      (node (ref "IC8") (pin "41") (pinfunction "SCKI_41") (pintype "bidirectional"))
      (node (ref "R45") (pin "2") (pinfunction "2_2") (pintype "passive"))
      (node (ref "R55") (pin "1") (pinfunction "1_1") (pintype "passive"))
    )
    (net (code "67") (name "H_SDI") (class "Default")
      (node (ref "IC8") (pin "42") (pinfunction "SDI_42") (pintype "bidirectional"))
      (node (ref "R47") (pin "2") (pinfunction "2_2") (pintype "passive"))
      (node (ref "R56") (pin "1") (pinfunction "1_1") (pintype "passive"))
    )
    (net (code "68") (name "H_SDO") (class "Default")
      (node (ref "IC8") (pin "43") (pinfunction "SDO_43") (pintype "bidirectional"))
      (node (ref "R46") (pin "2") (pinfunction "2_2") (pintype "passive"))
      (node (ref "R57") (pin "1") (pinfunction "1_1") (pintype "passive"))
    )
    (net (code "69") (name "H_SWCLK") (class "Default")
      (node (ref "IC7") (pin "29") (pinfunction "PIO0_10/SWCLK/SCK0/CT16B0_MAT2_29") (pintype "bidirectional"))
      (node (ref "JP2") (pin "4") (pinfunction "4_4") (pintype "passive"))
    )
    (net (code "70") (name "H_SWDIO") (class "Default")
      (node (ref "IC7") (pin "39") (pinfunction "PIO1_3/SWDIO/AD4/CT32B1_MAT2_39") (pintype "bidirectional"))
      (node (ref "JP2") (pin "3") (pinfunction "3_3") (pintype "passive"))
    )
    (net (code "71") (name "H_V+") (class "Default")
      (node (ref "C35") (pin "1") (pinfunction "1_1") (pintype "passive"))
      (node (ref "D3") (pin "C") (pinfunction "C_C") (pintype "passive"))
      (node (ref "IC8") (pin "1") (pinfunction "V+_1") (pintype "bidirectional"))
      (node (ref "Q6") (pin "3") (pinfunction "D_3") (pintype "passive"))
      (node (ref "R10") (pin "2") (pinfunction "2_2") (pintype "passive"))
    )
    (net (code "72") (name "H_VREF") (class "Default")
      (node (ref "CVREF1") (pin "2") (pinfunction "2_2") (pintype "passive"))
      (node (ref "IC8") (pin "31") (pinfunction "VREF_31") (pintype "bidirectional"))
    )
    (net (code "73") (name "H_VREG") (class "Default")
      (node (ref "CVREG1") (pin "2") (pinfunction "2_2") (pintype "passive"))
      (node (ref "IC8") (pin "32") (pinfunction "VREG_32") (pintype "bidirectional"))
      (node (ref "R55") (pin "2") (pinfunction "2_2") (pintype "passive"))
      (node (ref "R56") (pin "2") (pinfunction "2_2") (pintype "passive"))
      (node (ref "R57") (pin "2") (pinfunction "2_2") (pintype "passive"))
      (node (ref "R58") (pin "2") (pinfunction "2_2") (pintype "passive"))
    )
    (net (code "74") (name "H_~{RESET}") (class "Default")
      (node (ref "C24") (pin "1") (pinfunction "1_1") (pintype "passive"))
      (node (ref "IC7") (pin "3") (pinfunction "PIO0_0/~{RESET}_3") (pintype "bidirectional"))
      (node (ref "JP2") (pin "1") (pinfunction "1_1") (pintype "passive"))
      (node (ref "R9") (pin "2") (pinfunction "2_2") (pintype "passive"))
    )
    (net (code "75") (name "L+3V3") (class "Default")
      (node (ref "C10") (pin "1") (pinfunction "1_1") (pintype "passive"))
      (node (ref "C11") (pin "1") (pinfunction "1_1") (pintype "passive"))
      (node (ref "C22") (pin "1") (pinfunction "1_1") (pintype "passive"))
      (node (ref "C23") (pin "1") (pinfunction "1_1") (pintype "passive"))
      (node (ref "C27") (pin "1") (pinfunction "1_1") (pintype "passive"))
      (node (ref "C30") (pin "1") (pinfunction "1_1") (pintype "passive"))
      (node (ref "IC1") (pin "44") (pinfunction "VDD_44") (pintype "bidirectional"))
      (node (ref "IC1") (pin "8") (pinfunction "VDD_8") (pintype "bidirectional"))
      (node (ref "IC2") (pin "30") (pinfunction "VTEMP2_30") (pintype "bidirectional"))
      (node (ref "IC6") (pin "8") (pinfunction "VDD2_8") (pintype "bidirectional"))
      (node (ref "JP1") (pin "2") (pinfunction "2_2") (pintype "passive"))
      (node (ref "L12") (pin "1") (pinfunction "1_1") (pintype "passive"))
      (node (ref "LED18") (pin "A") (pinfunction "A_A") (pintype "passive"))
      (node (ref "LED2") (pin "A") (pinfunction "A_A") (pintype "passive"))
      (node (ref "NTC_R3") (pin "2") (pinfunction "2_2") (pintype "passive"))
      (node (ref "NTC_R4") (pin "2") (pinfunction "2_2") (pintype "passive"))
      (node (ref "Q2") (pin "1") (pinfunction "G_1") (pintype "passive"))
      (node (ref "R15") (pin "1") (pinfunction "1_1") (pintype "passive"))
      (node (ref "R23") (pin "2") (pinfunction "2_2") (pintype "passive"))
      (node (ref "R52") (pin "1") (pinfunction "1_1") (pintype "passive"))
      (node (ref "RGQ1_3") (pin "2") (pinfunction "2_2") (pintype "passive"))
    )
    (net (code "76") (name "LGND") (class "Default")
      (node (ref "C1") (pin "2") (pinfunction "2_2") (pintype "passive"))
      (node (ref "C10") (pin "2") (pinfunction "2_2") (pintype "passive"))
      (node (ref "C11") (pin "2") (pinfunction "2_2") (pintype "passive"))
      (node (ref "C14") (pin "1") (pinfunction "1_1") (pintype "passive"))
      (node (ref "C15") (pin "1") (pinfunction "1_1") (pintype "passive"))
      (node (ref "C22") (pin "2") (pinfunction "2_2") (pintype "passive"))
      (node (ref "C23") (pin "2") (pinfunction "2_2") (pintype "passive"))
      (node (ref "C27") (pin "2") (pinfunction "2_2") (pintype "passive"))
      (node (ref "C29") (pin "2") (pinfunction "2_2") (pintype "passive"))
      (node (ref "C30") (pin "2") (pinfunction "2_2") (pintype "passive"))
      (node (ref "C34") (pin "2") (pinfunction "2_2") (pintype "passive"))
      (node (ref "CFSM") (pin "1") (pinfunction "1_1") (pintype "passive"))
      (node (ref "CVREF") (pin "1") (pinfunction "1_1") (pintype "passive"))
      (node (ref "CVREG") (pin "1") (pinfunction "1_1") (pintype "passive"))
      (node (ref "D1") (pin "A") (pinfunction "A_A") (pintype "passive"))
      (node (ref "DCDC2") (pin "4") (pinfunction "VOUT-_4") (pintype "bidirectional"))
      (node (ref "IC1") (pin "41") (pinfunction "VSS_41") (pintype "bidirectional"))
      (node (ref "IC1") (pin "5") (pinfunction "VSS_5") (pintype "bidirectional"))
      (node (ref "IC2") (pin "27") (pinfunction "V-_27") (pintype "bidirectional"))
      (node (ref "IC2") (pin "33") (pinfunction "TOS_33") (pintype "bidirectional"))
      (node (ref "IC2") (pin "34") (pinfunction "WDTB_34") (pintype "bidirectional"))
      (node (ref "IC2") (pin "35") (pinfunction "GPIO1_35") (pintype "bidirectional"))
      (node (ref "IC2") (pin "36") (pinfunction "GPIO2_36") (pintype "bidirectional"))
      (node (ref "IC2") (pin "37") (pinfunction "A0_37") (pintype "bidirectional"))
      (node (ref "IC2") (pin "38") (pinfunction "A1_38") (pintype "bidirectional"))
      (node (ref "IC2") (pin "39") (pinfunction "A2_39") (pintype "bidirectional"))
      (node (ref "IC2") (pin "40") (pinfunction "A3_40") (pintype "bidirectional"))
      (node (ref "IC6") (pin "5") (pinfunction "GND2_5") (pintype "bidirectional"))
      (node (ref "JP1") (pin "6") (pinfunction "6_6") (pintype "passive"))
      (node (ref "L_V-R") (pin "2") (pinfunction "2_2") (pintype "passive"))
      (node (ref "NTC_C3") (pin "2") (pinfunction "2_2") (pintype "passive"))
      (node (ref "NTC_C4") (pin "2") (pinfunction "2_2") (pintype "passive"))
      (node (ref "Q2") (pin "2") (pinfunction "S_2") (pintype "passive"))
      (node (ref "Q4") (pin "2") (pinfunction "S_2") (pintype "passive"))
      (node (ref "R11") (pin "1") (pinfunction "1_1") (pintype "passive"))
      (node (ref "R2") (pin "1") (pinfunction "1_1") (pintype "passive"))
      (node (ref "R42") (pin "1") (pinfunction "1_1") (pintype "passive"))
      (node (ref "R60") (pin "1") (pinfunction "1_1") (pintype "passive"))
      (node (ref "RGQ1_3") (pin "1") (pinfunction "1_1") (pintype "passive"))
      (node (ref "X5") (pin "1") (pinfunction "S_1") (pintype "passive"))
      (node (ref "X5") (pin "3") (pinfunction "S_3") (pintype "passive"))
    )
    (net (code "77") (name "L_AD1") (class "Default")
      (node (ref "IC1") (pin "33") (pinfunction "PIO1_0/AD1/CT32B1_CAP0_33") (pintype "bidirectional"))
      (node (ref "NTC_C3") (pin "1") (pinfunction "1_1") (pintype "passive"))
      (node (ref "NTC_R3") (pin "1") (pinfunction "1_1") (pintype "passive"))
      (node (ref "X5") (pin "2") (pinfunction "S_2") (pintype "passive"))
    )
    (net (code "78") (name "L_AD2") (class "Default")
      (node (ref "IC1") (pin "34") (pinfunction "PIO1_1/AD2/CT32B1_MAT0_34") (pintype "bidirectional"))
      (node (ref "NTC_C4") (pin "1") (pinfunction "1_1") (pintype "passive"))
      (node (ref "NTC_R4") (pin "1") (pinfunction "1_1") (pintype "passive"))
      (node (ref "X5") (pin "4") (pinfunction "S_4") (pintype "passive"))
    )
    (net (code "79") (name "L_CANRX") (class "Default")
      (node (ref "IC6") (pin "6") (pinfunction "O2_6") (pintype "bidirectional"))
      (node (ref "R7") (pin "2") (pinfunction "2_2") (pintype "passive"))
    )
    (net (code "80") (name "L_CANTX") (class "Default")
      (node (ref "IC6") (pin "7") (pinfunction "I1_7") (pintype "bidirectional"))
      (node (ref "R6") (pin "2") (pinfunction "2_2") (pintype "passive"))
    )
    (net (code "81") (name "L_CSB") (class "Default")
      (node (ref "IC2") (pin "44") (pinfunction "CSBI_44") (pintype "bidirectional"))
      (node (ref "R1") (pin "2") (pinfunction "2_2") (pintype "passive"))
      (node (ref "R20") (pin "1") (pinfunction "1_1") (pintype "passive"))
    )
    (net (code "82") (name "L_FSM") (class "Default")
      (node (ref "CFSM") (pin "2") (pinfunction "2_2") (pintype "passive"))
      (node (ref "IC2") (pin "29") (pinfunction "VTEMP1_29") (pintype "bidirectional"))
      (node (ref "R59") (pin "1") (pinfunction "1_1") (pintype "passive"))
      (node (ref "R60") (pin "2") (pinfunction "2_2") (pintype "passive"))
    )
    (net (code "83") (name "L_ISP_CAN") (class "Default")
      (node (ref "IC1") (pin "14") (pinfunction "PIO0_3_14") (pintype "bidirectional"))
      (node (ref "R11") (pin "2") (pinfunction "2_2") (pintype "passive"))
    )
    (net (code "84") (name "L_ISP_ENTER") (class "Default")
      (node (ref "IC1") (pin "4") (pinfunction "PIO0_1/CLKOUT/CT32B0_MAT2_4") (pintype "bidirectional"))
      (node (ref "JP1") (pin "5") (pinfunction "5_5") (pintype "passive"))
      (node (ref "R15") (pin "2") (pinfunction "2_2") (pintype "passive"))
    )
    (net (code "85") (name "L_LED") (class "Default")
      (node (ref "IC1") (pin "48") (pinfunction "PIO3_3/~{RI}_48") (pintype "bidirectional"))
      (node (ref "Q4") (pin "1") (pinfunction "G_1") (pintype "passive"))
    )
    (net (code "86") (name "L_SCK") (class "Default")
      (node (ref "IC2") (pin "41") (pinfunction "SCKI_41") (pintype "bidirectional"))
      (node (ref "R17") (pin "1") (pinfunction "1_1") (pintype "passive"))
      (node (ref "R3") (pin "2") (pinfunction "2_2") (pintype "passive"))
    )
    (net (code "87") (name "L_SDI") (class "Default")
      (node (ref "IC2") (pin "42") (pinfunction "SDI_42") (pintype "bidirectional"))
      (node (ref "R18") (pin "1") (pinfunction "1_1") (pintype "passive"))
      (node (ref "R5") (pin "2") (pinfunction "2_2") (pintype "passive"))
    )
    (net (code "88") (name "L_SDO") (class "Default")
      (node (ref "IC2") (pin "43") (pinfunction "SDO_43") (pintype "bidirectional"))
      (node (ref "R19") (pin "1") (pinfunction "1_1") (pintype "passive"))
      (node (ref "R4") (pin "2") (pinfunction "2_2") (pintype "passive"))
    )
    (net (code "89") (name "L_SWCLK") (class "Default")
      (node (ref "IC1") (pin "29") (pinfunction "PIO0_10/SWCLK/SCK0/CT16B0_MAT2_29") (pintype "bidirectional"))
      (node (ref "JP1") (pin "4") (pinfunction "4_4") (pintype "passive"))
    )
    (net (code "90") (name "L_SWDIO") (class "Default")
      (node (ref "IC1") (pin "39") (pinfunction "PIO1_3/SWDIO/AD4/CT32B1_MAT2_39") (pintype "bidirectional"))
      (node (ref "JP1") (pin "3") (pinfunction "3_3") (pintype "passive"))
    )
    (net (code "91") (name "L_V+") (class "Default")
      (node (ref "C1") (pin "1") (pinfunction "1_1") (pintype "passive"))
      (node (ref "D1") (pin "C") (pinfunction "C_C") (pintype "passive"))
      (node (ref "IC2") (pin "1") (pinfunction "V+_1") (pintype "bidirectional"))
      (node (ref "Q1") (pin "3") (pinfunction "D_3") (pintype "passive"))
      (node (ref "R59") (pin "2") (pinfunction "2_2") (pintype "passive"))
    )
    (net (code "92") (name "L_VREF") (class "Default")
      (node (ref "CVREF") (pin "2") (pinfunction "2_2") (pintype "passive"))
      (node (ref "IC2") (pin "31") (pinfunction "VREF_31") (pintype "bidirectional"))
    )
    (net (code "93") (name "L_VREG") (class "Default")
      (node (ref "CVREG") (pin "2") (pinfunction "2_2") (pintype "passive"))
      (node (ref "IC2") (pin "32") (pinfunction "VREG_32") (pintype "bidirectional"))
      (node (ref "R17") (pin "2") (pinfunction "2_2") (pintype "passive"))
      (node (ref "R18") (pin "2") (pinfunction "2_2") (pintype "passive"))
      (node (ref "R19") (pin "2") (pinfunction "2_2") (pintype "passive"))
      (node (ref "R20") (pin "2") (pinfunction "2_2") (pintype "passive"))
    )
    (net (code "94") (name "L_~{RESET}") (class "Default")
      (node (ref "C34") (pin "1") (pinfunction "1_1") (pintype "passive"))
      (node (ref "IC1") (pin "3") (pinfunction "PIO0_0/~{RESET}_3") (pintype "bidirectional"))
      (node (ref "JP1") (pin "1") (pinfunction "1_1") (pintype "passive"))
      (node (ref "R52") (pin "2") (pinfunction "2_2") (pintype "passive"))
    )
    (net (code "95") (name "Net-(C16-Pad1)") (class "Default")
      (node (ref "C16") (pin "1") (pinfunction "1_1") (pintype "passive"))
      (node (ref "R21") (pin "1") (pinfunction "1_1") (pintype "passive"))
      (node (ref "R22") (pin "1") (pinfunction "1_1") (pintype "passive"))
    )
    (net (code "96") (name "Net-(DCDC1-VIN+)") (class "Default")
      (node (ref "DCDC1") (pin "2") (pinfunction "VIN+_2") (pintype "bidirectional"))
      (node (ref "DCDC2") (pin "2") (pinfunction "VIN+_2") (pintype "bidirectional"))
      (node (ref "DCIN") (pin "3") (pinfunction "VO_3") (pintype "bidirectional"))
      (node (ref "L3") (pin "2") (pinfunction "2_2") (pintype "passive"))
      (node (ref "L4") (pin "2") (pinfunction "2_2") (pintype "passive"))
    )
    (net (code "97") (name "Net-(DCDC1-VOUT+)") (class "Default")
      (node (ref "C4") (pin "1") (pinfunction "1_1") (pintype "passive"))
      (node (ref "DCDC1") (pin "5") (pinfunction "VOUT+_5") (pintype "bidirectional"))
      (node (ref "L2") (pin "2") (pinfunction "2_2") (pintype "passive"))
    )
    (net (code "98") (name "Net-(DCDC2-VOUT+)") (class "Default")
      (node (ref "C29") (pin "1") (pinfunction "1_1") (pintype "passive"))
      (node (ref "DCDC2") (pin "5") (pinfunction "VOUT+_5") (pintype "bidirectional"))
      (node (ref "L12") (pin "2") (pinfunction "2_2") (pintype "passive"))
    )
    (net (code "99") (name "Net-(IC1-CANRX)") (class "Default")
      (node (ref "IC1") (pin "19") (pinfunction "CANRX_19") (pintype "bidirectional"))
      (node (ref "R7") (pin "1") (pinfunction "1_1") (pintype "passive"))
    )
    (net (code "100") (name "Net-(IC1-CANTX)") (class "Default")
      (node (ref "IC1") (pin "20") (pinfunction "CANTX_20") (pintype "bidirectional"))
      (node (ref "R6") (pin "1") (pinfunction "1_1") (pintype "passive"))
    )
    (net (code "101") (name "Net-(IC1-PIO0_11{slash}AD0{slash}CT32B0_MAT3)") (class "Default")
      (node (ref "IC1") (pin "32") (pinfunction "PIO0_11/AD0/CT32B0_MAT3_32") (pintype "bidirectional"))
      (node (ref "R2") (pin "2") (pinfunction "2_2") (pintype "passive"))
      (node (ref "R23") (pin "1") (pinfunction "1_1") (pintype "passive"))
    )
    (net (code "102") (name "Net-(IC1-PIO2_0{slash}~{DTR}{slash}SSEL1)") (class "Default")
      (node (ref "IC1") (pin "2") (pinfunction "PIO2_0/~{DTR}/SSEL1_2") (pintype "bidirectional"))
      (node (ref "R1") (pin "1") (pinfunction "1_1") (pintype "passive"))
    )
    (net (code "103") (name "Net-(IC1-PIO2_1{slash}~{DSR}{slash}SCK1)") (class "Default")
      (node (ref "IC1") (pin "13") (pinfunction "PIO2_1/~{DSR}/SCK1_13") (pintype "bidirectional"))
      (node (ref "R3") (pin "1") (pinfunction "1_1") (pintype "passive"))
    )
    (net (code "104") (name "Net-(IC1-PIO2_2{slash}~{DCD}{slash}MISO1)") (class "Default")
      (node (ref "IC1") (pin "26") (pinfunction "PIO2_2/~{DCD}/MISO1_26") (pintype "bidirectional"))
      (node (ref "R4") (pin "1") (pinfunction "1_1") (pintype "passive"))
    )
    (net (code "105") (name "Net-(IC1-PIO2_3{slash}~{RI}{slash}MOSI1)") (class "Default")
      (node (ref "IC1") (pin "38") (pinfunction "PIO2_3/~{RI}/MOSI1_38") (pintype "bidirectional"))
      (node (ref "R5") (pin "1") (pinfunction "1_1") (pintype "passive"))
    )
    (net (code "106") (name "Net-(IC1-XTALIN)") (class "Default")
      (node (ref "C15") (pin "2") (pinfunction "2_2") (pintype "passive"))
      (node (ref "IC1") (pin "6") (pinfunction "XTALIN_6") (pintype "bidirectional"))
      (node (ref "Y1") (pin "2") (pinfunction "2_2") (pintype "passive"))
    )
    (net (code "107") (name "Net-(IC1-XTALOUT)") (class "Default")
      (node (ref "C14") (pin "2") (pinfunction "2_2") (pintype "passive"))
      (node (ref "IC1") (pin "7") (pinfunction "XTALOUT_7") (pintype "bidirectional"))
      (node (ref "Y1") (pin "1") (pinfunction "1_1") (pintype "passive"))
    )
    (net (code "108") (name "Net-(IC3-I2)") (class "Default")
      (node (ref "IC3") (pin "3") (pinfunction "I2_3") (pintype "bidirectional"))
      (node (ref "R14") (pin "2") (pinfunction "2_2") (pintype "passive"))
    )
    (net (code "109") (name "Net-(IC3-O1)") (class "Default")
      (node (ref "IC3") (pin "2") (pinfunction "O1_2") (pintype "bidirectional"))
      (node (ref "R13") (pin "2") (pinfunction "2_2") (pintype "passive"))
    )
    (net (code "110") (name "Net-(IC3-VDD1)") (class "Default")
      (node (ref "C18") (pin "1") (pinfunction "1_1") (pintype "passive"))
      (node (ref "C6") (pin "1") (pinfunction "1_1") (pintype "passive"))
      (node (ref "C7") (pin "1") (pinfunction "1_1") (pintype "passive"))
      (node (ref "IC3") (pin "1") (pinfunction "VDD1_1") (pintype "bidirectional"))
      (node (ref "IC4") (pin "3") (pinfunction "VDD_3") (pintype "bidirectional"))
      (node (ref "L3") (pin "1") (pinfunction "1_1") (pintype "passive"))
    )
    (net (code "111") (name "Net-(IC4-CANH)") (class "Default")
      (node (ref "IC4") (pin "7") (pinfunction "CANH_7") (pintype "bidirectional"))
      (node (ref "L8") (pin "5") (pinfunction "2_5") (pintype "passive"))
    )
    (net (code "112") (name "Net-(IC4-CANL)") (class "Default")
      (node (ref "IC4") (pin "6") (pinfunction "CANL_6") (pintype "bidirectional"))
      (node (ref "L8") (pin "4") (pinfunction "4_4") (pintype "passive"))
    )
    (net (code "113") (name "Net-(IC4-RS)") (class "Default")
      (node (ref "IC4") (pin "8") (pinfunction "RS_8") (pintype "bidirectional"))
      (node (ref "R12") (pin "1") (pinfunction "1_1") (pintype "passive"))
    )
    (net (code "114") (name "Net-(IC4-RX)") (class "Default")
      (node (ref "IC4") (pin "4") (pinfunction "RX_4") (pintype "bidirectional"))
      (node (ref "R14") (pin "1") (pinfunction "1_1") (pintype "passive"))
    )
    (net (code "115") (name "Net-(IC4-TX)") (class "Default")
      (node (ref "IC4") (pin "1") (pinfunction "TX_1") (pintype "bidirectional"))
      (node (ref "R13") (pin "1") (pinfunction "1_1") (pintype "passive"))
    )
    (net (code "116") (name "Net-(IC5-CANH)") (class "Default")
      (node (ref "IC5") (pin "7") (pinfunction "CANH_7") (pintype "bidirectional"))
      (node (ref "L11") (pin "5") (pinfunction "2_5") (pintype "passive"))
    )
    (net (code "117") (name "Net-(IC5-CANL)") (class "Default")
      (node (ref "IC5") (pin "6") (pinfunction "CANL_6") (pintype "bidirectional"))
      (node (ref "L11") (pin "4") (pinfunction "4_4") (pintype "passive"))
    )
    (net (code "118") (name "Net-(IC5-RS)") (class "Default")
      (node (ref "IC5") (pin "8") (pinfunction "RS_8") (pintype "bidirectional"))
      (node (ref "R39") (pin "1") (pinfunction "1_1") (pintype "passive"))
    )
    (net (code "119") (name "Net-(IC5-RX)") (class "Default")
      (node (ref "IC5") (pin "4") (pinfunction "RX_4") (pintype "bidirectional"))
      (node (ref "R41") (pin "1") (pinfunction "1_1") (pintype "passive"))
    )
    (net (code "120") (name "Net-(IC5-TX)") (class "Default")
      (node (ref "IC5") (pin "1") (pinfunction "TX_1") (pintype "bidirectional"))
      (node (ref "R40") (pin "1") (pinfunction "1_1") (pintype "passive"))
    )
    (net (code "121") (name "Net-(IC5-VDD)") (class "Default")
      (node (ref "C17") (pin "1") (pinfunction "1_1") (pintype "passive"))
      (node (ref "C20") (pin "1") (pinfunction "1_1") (pintype "passive"))
      (node (ref "C26") (pin "1") (pinfunction "1_1") (pintype "passive"))
      (node (ref "IC5") (pin "3") (pinfunction "VDD_3") (pintype "bidirectional"))
      (node (ref "IC6") (pin "1") (pinfunction "VDD1_1") (pintype "bidirectional"))
      (node (ref "L4") (pin "1") (pinfunction "1_1") (pintype "passive"))
    )
    (net (code "122") (name "Net-(IC6-I2)") (class "Default")
      (node (ref "IC6") (pin "3") (pinfunction "I2_3") (pintype "bidirectional"))
      (node (ref "R41") (pin "2") (pinfunction "2_2") (pintype "passive"))
    )
    (net (code "123") (name "Net-(IC6-O1)") (class "Default")
      (node (ref "IC6") (pin "2") (pinfunction "O1_2") (pintype "bidirectional"))
      (node (ref "R40") (pin "2") (pinfunction "2_2") (pintype "passive"))
    )
    (net (code "124") (name "Net-(IC7-CANRX)") (class "Default")
      (node (ref "IC7") (pin "19") (pinfunction "CANRX_19") (pintype "bidirectional"))
      (node (ref "R49") (pin "1") (pinfunction "1_1") (pintype "passive"))
    )
    (net (code "125") (name "Net-(IC7-CANTX)") (class "Default")
      (node (ref "IC7") (pin "20") (pinfunction "CANTX_20") (pintype "bidirectional"))
      (node (ref "R48") (pin "1") (pinfunction "1_1") (pintype "passive"))
    )
    (net (code "126") (name "Net-(IC7-PIO0_11{slash}AD0{slash}CT32B0_MAT3)") (class "Default")
      (node (ref "IC7") (pin "32") (pinfunction "PIO0_11/AD0/CT32B0_MAT3_32") (pintype "bidirectional"))
      (node (ref "R24") (pin "2") (pinfunction "2_2") (pintype "passive"))
      (node (ref "R25") (pin "1") (pinfunction "1_1") (pintype "passive"))
    )
    (net (code "127") (name "Net-(IC7-PIO2_0{slash}~{DTR}{slash}SSEL1)") (class "Default")
      (node (ref "IC7") (pin "2") (pinfunction "PIO2_0/~{DTR}/SSEL1_2") (pintype "bidirectional"))
      (node (ref "R44") (pin "1") (pinfunction "1_1") (pintype "passive"))
    )
    (net (code "128") (name "Net-(IC7-PIO2_1{slash}~{DSR}{slash}SCK1)") (class "Default")
      (node (ref "IC7") (pin "13") (pinfunction "PIO2_1/~{DSR}/SCK1_13") (pintype "bidirectional"))
      (node (ref "R45") (pin "1") (pinfunction "1_1") (pintype "passive"))
    )
    (net (code "129") (name "Net-(IC7-PIO2_2{slash}~{DCD}{slash}MISO1)") (class "Default")
      (node (ref "IC7") (pin "26") (pinfunction "PIO2_2/~{DCD}/MISO1_26") (pintype "bidirectional"))
      (node (ref "R46") (pin "1") (pinfunction "1_1") (pintype "passive"))
    )
    (net (code "130") (name "Net-(IC7-PIO2_3{slash}~{RI}{slash}MOSI1)") (class "Default")
      (node (ref "IC7") (pin "38") (pinfunction "PIO2_3/~{RI}/MOSI1_38") (pintype "bidirectional"))
      (node (ref "R47") (pin "1") (pinfunction "1_1") (pintype "passive"))
    )
    (net (code "131") (name "Net-(IC7-XTALIN)") (class "Default")
      (node (ref "C31") (pin "2") (pinfunction "2_2") (pintype "passive"))
      (node (ref "IC7") (pin "6") (pinfunction "XTALIN_6") (pintype "bidirectional"))
      (node (ref "Y2") (pin "2") (pinfunction "2_2") (pintype "passive"))
    )
    (net (code "132") (name "Net-(IC7-XTALOUT)") (class "Default")
      (node (ref "C25") (pin "2") (pinfunction "2_2") (pintype "passive"))
      (node (ref "IC7") (pin "7") (pinfunction "XTALOUT_7") (pintype "bidirectional"))
      (node (ref "Y2") (pin "1") (pinfunction "1_1") (pintype "passive"))
    )
    (net (code "133") (name "Net-(L5-Pad2)") (class "Default")
      (node (ref "L5") (pin "2") (pinfunction "2_2") (pintype "passive"))
      (node (ref "V+R1") (pin "1") (pinfunction "1_1") (pintype "passive"))
    )
    (net (code "134") (name "Net-(L7-Pad2)") (class "Default")
      (node (ref "L7") (pin "2") (pinfunction "2_2") (pintype "passive"))
      (node (ref "V+R") (pin "1") (pinfunction "1_1") (pintype "passive"))
    )
    (net (code "135") (name "Net-(LED1-PadC)") (class "Default")
      (node (ref "LED1") (pin "C") (pinfunction "C_C") (pintype "passive"))
      (node (ref "R8") (pin "2") (pinfunction "2_2") (pintype "passive"))
    )
    (net (code "136") (name "Net-(LED2-PadC)") (class "Default")
      (node (ref "LED2") (pin "C") (pinfunction "C_C") (pintype "passive"))
      (node (ref "R53") (pin "2") (pinfunction "2_2") (pintype "passive"))
    )
    (net (code "137") (name "Net-(LED18-PadC)") (class "Default")
      (node (ref "LED18") (pin "C") (pinfunction "C_C") (pintype "passive"))
      (node (ref "R42") (pin "2") (pinfunction "2_2") (pintype "passive"))
    )
    (net (code "138") (name "Net-(LED19-PadC)") (class "Default")
      (node (ref "LED19") (pin "C") (pinfunction "C_C") (pintype "passive"))
      (node (ref "R43") (pin "2") (pinfunction "2_2") (pintype "passive"))
    )
    (net (code "139") (name "Net-(Q1-G)") (class "Default")
      (node (ref "D2") (pin "A") (pinfunction "A_A") (pintype "passive"))
      (node (ref "Q1") (pin "1") (pinfunction "G_1") (pintype "passive"))
      (node (ref "RGQ1_1") (pin "2") (pinfunction "2_2") (pintype "passive"))
      (node (ref "RGQ1_2") (pin "2") (pinfunction "2_2") (pintype "passive"))
    )
    (net (code "140") (name "Net-(Q1-S)") (class "Default")
      (node (ref "D2") (pin "C") (pinfunction "C_C") (pintype "passive"))
      (node (ref "Q1") (pin "2") (pinfunction "S_2") (pintype "passive"))
      (node (ref "RGQ1_1") (pin "1") (pinfunction "1_1") (pintype "passive"))
      (node (ref "V+R") (pin "2") (pinfunction "2_2") (pintype "passive"))
    )
    (net (code "141") (name "Net-(Q2-D)") (class "Default")
      (node (ref "Q2") (pin "3") (pinfunction "D_3") (pintype "passive"))
      (node (ref "RGQ1_2") (pin "1") (pinfunction "1_1") (pintype "passive"))
    )
    (net (code "142") (name "Net-(Q3-D)") (class "Default")
      (node (ref "Q3") (pin "3") (pinfunction "D_3") (pintype "passive"))
      (node (ref "R8") (pin "1") (pinfunction "1_1") (pintype "passive"))
    )
    (net (code "143") (name "Net-(Q4-D)") (class "Default")
      (node (ref "Q4") (pin "3") (pinfunction "D_3") (pintype "passive"))
      (node (ref "R53") (pin "1") (pinfunction "1_1") (pintype "passive"))
    )
    (net (code "144") (name "Net-(Q5-D)") (class "Default")
      (node (ref "Q5") (pin "3") (pinfunction "D_3") (pintype "passive"))
      (node (ref "RGQ1_5") (pin "1") (pinfunction "1_1") (pintype "passive"))
    )
    (net (code "145") (name "Net-(Q6-G)") (class "Default")
      (node (ref "D4") (pin "A") (pinfunction "A_A") (pintype "passive"))
      (node (ref "Q6") (pin "1") (pinfunction "G_1") (pintype "passive"))
      (node (ref "RGQ1_4") (pin "2") (pinfunction "2_2") (pintype "passive"))
      (node (ref "RGQ1_5") (pin "2") (pinfunction "2_2") (pintype "passive"))
    )
    (net (code "146") (name "Net-(Q6-S)") (class "Default")
      (node (ref "D4") (pin "C") (pinfunction "C_C") (pintype "passive"))
      (node (ref "Q6") (pin "2") (pinfunction "S_2") (pintype "passive"))
      (node (ref "RGQ1_4") (pin "1") (pinfunction "1_1") (pintype "passive"))
      (node (ref "V+R1") (pin "2") (pinfunction "2_2") (pintype "passive"))
    )
    (net (code "147") (name "Net-(QB1-D)") (class "Default")
      (node (ref "QB1") (pin "3") (pinfunction "D_3") (pintype "passive"))
      (node (ref "RP1") (pin "2") (pinfunction "2_2") (pintype "passive"))
    )
    (net (code "148") (name "Net-(QB1-G)") (class "Default")
      (node (ref "QB1") (pin "1") (pinfunction "G_1") (pintype "passive"))
      (node (ref "RBG1") (pin "1") (pinfunction "1_1") (pintype "passive"))
    )
    (net (code "149") (name "Net-(QB2-D)") (class "Default")
      (node (ref "QB2") (pin "3") (pinfunction "D_3") (pintype "passive"))
      (node (ref "RP2") (pin "2") (pinfunction "2_2") (pintype "passive"))
    )
    (net (code "150") (name "Net-(QB2-G)") (class "Default")
      (node (ref "QB2") (pin "1") (pinfunction "G_1") (pintype "passive"))
      (node (ref "RBG2") (pin "1") (pinfunction "1_1") (pintype "passive"))
    )
    (net (code "151") (name "Net-(QB3-D)") (class "Default")
      (node (ref "QB3") (pin "3") (pinfunction "D_3") (pintype "passive"))
      (node (ref "RP3") (pin "2") (pinfunction "2_2") (pintype "passive"))
    )
    (net (code "152") (name "Net-(QB3-G)") (class "Default")
      (node (ref "QB3") (pin "1") (pinfunction "G_1") (pintype "passive"))
      (node (ref "RBG3") (pin "1") (pinfunction "1_1") (pintype "passive"))
    )
    (net (code "153") (name "Net-(QB4-D)") (class "Default")
      (node (ref "QB4") (pin "3") (pinfunction "D_3") (pintype "passive"))
      (node (ref "RP4") (pin "2") (pinfunction "2_2") (pintype "passive"))
    )
    (net (code "154") (name "Net-(QB4-G)") (class "Default")
      (node (ref "QB4") (pin "1") (pinfunction "G_1") (pintype "passive"))
      (node (ref "RBG4") (pin "1") (pinfunction "1_1") (pintype "passive"))
    )
    (net (code "155") (name "Net-(QB5-D)") (class "Default")
      (node (ref "QB5") (pin "3") (pinfunction "D_3") (pintype "passive"))
      (node (ref "RP5") (pin "2") (pinfunction "2_2") (pintype "passive"))
    )
    (net (code "156") (name "Net-(QB5-G)") (class "Default")
      (node (ref "QB5") (pin "1") (pinfunction "G_1") (pintype "passive"))
      (node (ref "RBG5") (pin "1") (pinfunction "1_1") (pintype "passive"))
    )
    (net (code "157") (name "Net-(QB6-D)") (class "Default")
      (node (ref "QB6") (pin "3") (pinfunction "D_3") (pintype "passive"))
      (node (ref "RP6") (pin "2") (pinfunction "2_2") (pintype "passive"))
    )
    (net (code "158") (name "Net-(QB6-G)") (class "Default")
      (node (ref "QB6") (pin "1") (pinfunction "G_1") (pintype "passive"))
      (node (ref "RBG6") (pin "1") (pinfunction "1_1") (pintype "passive"))
    )
    (net (code "159") (name "Net-(QB7-D)") (class "Default")
      (node (ref "QB7") (pin "3") (pinfunction "D_3") (pintype "passive"))
      (node (ref "RP7") (pin "2") (pinfunction "2_2") (pintype "passive"))
    )
    (net (code "160") (name "Net-(QB7-G)") (class "Default")
      (node (ref "QB7") (pin "1") (pinfunction "G_1") (pintype "passive"))
      (node (ref "RBG7") (pin "1") (pinfunction "1_1") (pintype "passive"))
    )
    (net (code "161") (name "Net-(QB8-D)") (class "Default")
      (node (ref "QB8") (pin "3") (pinfunction "D_3") (pintype "passive"))
      (node (ref "RP8") (pin "2") (pinfunction "2_2") (pintype "passive"))
    )
    (net (code "162") (name "Net-(QB8-G)") (class "Default")
      (node (ref "QB8") (pin "1") (pinfunction "G_1") (pintype "passive"))
      (node (ref "RBG8") (pin "1") (pinfunction "1_1") (pintype "passive"))
    )
    (net (code "163") (name "Net-(QB9-D)") (class "Default")
      (node (ref "QB9") (pin "3") (pinfunction "D_3") (pintype "passive"))
      (node (ref "RP9") (pin "2") (pinfunction "2_2") (pintype "passive"))
    )
    (net (code "164") (name "Net-(QB9-G)") (class "Default")
      (node (ref "QB9") (pin "1") (pinfunction "G_1") (pintype "passive"))
      (node (ref "RBG9") (pin "1") (pinfunction "1_1") (pintype "passive"))
    )
    (net (code "165") (name "Net-(QB10-D)") (class "Default")
      (node (ref "QB10") (pin "3") (pinfunction "D_3") (pintype "passive"))
      (node (ref "RP10") (pin "2") (pinfunction "2_2") (pintype "passive"))
    )
    (net (code "166") (name "Net-(QB10-G)") (class "Default")
      (node (ref "QB10") (pin "1") (pinfunction "G_1") (pintype "passive"))
      (node (ref "RBG10") (pin "1") (pinfunction "1_1") (pintype "passive"))
    )
    (net (code "167") (name "Net-(QB11-D)") (class "Default")
      (node (ref "QB11") (pin "3") (pinfunction "D_3") (pintype "passive"))
      (node (ref "RP11") (pin "2") (pinfunction "2_2") (pintype "passive"))
    )
    (net (code "168") (name "Net-(QB11-G)") (class "Default")
      (node (ref "QB11") (pin "1") (pinfunction "G_1") (pintype "passive"))
      (node (ref "RBG11") (pin "1") (pinfunction "1_1") (pintype "passive"))
    )
    (net (code "169") (name "Net-(QB12-D)") (class "Default")
      (node (ref "QB12") (pin "3") (pinfunction "D_3") (pintype "passive"))
      (node (ref "RP12") (pin "2") (pinfunction "2_2") (pintype "passive"))
    )
    (net (code "170") (name "Net-(QB12-G)") (class "Default")
      (node (ref "QB12") (pin "1") (pinfunction "G_1") (pintype "passive"))
      (node (ref "RBG12") (pin "1") (pinfunction "1_1") (pintype "passive"))
    )
    (net (code "171") (name "Net-(QB13-D)") (class "Default")
      (node (ref "QB13") (pin "3") (pinfunction "D_3") (pintype "passive"))
      (node (ref "RP13") (pin "2") (pinfunction "2_2") (pintype "passive"))
    )
    (net (code "172") (name "Net-(QB13-G)") (class "Default")
      (node (ref "QB13") (pin "1") (pinfunction "G_1") (pintype "passive"))
      (node (ref "RBG13") (pin "1") (pinfunction "1_1") (pintype "passive"))
    )
    (net (code "173") (name "Net-(QB14-D)") (class "Default")
      (node (ref "QB14") (pin "3") (pinfunction "D_3") (pintype "passive"))
      (node (ref "RP14") (pin "2") (pinfunction "2_2") (pintype "passive"))
    )
    (net (code "174") (name "Net-(QB14-G)") (class "Default")
      (node (ref "QB14") (pin "1") (pinfunction "G_1") (pintype "passive"))
      (node (ref "RBG14") (pin "1") (pinfunction "1_1") (pintype "passive"))
    )
    (net (code "175") (name "Net-(QB15-D)") (class "Default")
      (node (ref "QB15") (pin "3") (pinfunction "D_3") (pintype "passive"))
      (node (ref "RP15") (pin "2") (pinfunction "2_2") (pintype "passive"))
    )
    (net (code "176") (name "Net-(QB15-G)") (class "Default")
      (node (ref "QB15") (pin "1") (pinfunction "G_1") (pintype "passive"))
      (node (ref "RBG15") (pin "1") (pinfunction "1_1") (pintype "passive"))
    )
    (net (code "177") (name "Net-(QB16-D)") (class "Default")
      (node (ref "QB16") (pin "3") (pinfunction "D_3") (pintype "passive"))
      (node (ref "RP16") (pin "2") (pinfunction "2_2") (pintype "passive"))
    )
    (net (code "178") (name "Net-(QB16-G)") (class "Default")
      (node (ref "QB16") (pin "1") (pinfunction "G_1") (pintype "passive"))
      (node (ref "RBG16") (pin "1") (pinfunction "1_1") (pintype "passive"))
    )
    (net (code "179") (name "Net-(R21-Pad2)") (class "Default")
      (node (ref "R21") (pin "2") (pinfunction "2_2") (pintype "passive"))
      (node (ref "SJ1") (pin "1") (pinfunction "1_1") (pintype "passive"))
    )
    (net (code "180") (name "unconnected-(IC1-PIO0_2{slash}SSEL{slash}CT16B0_CAP0-Pad10)") (class "Default")
      (node (ref "IC1") (pin "10") (pinfunction "PIO0_2/SSEL/CT16B0_CAP0_10") (pintype "bidirectional"))
    )
    (net (code "181") (name "unconnected-(IC1-PIO0_4{slash}SCL-Pad15)") (class "Default")
      (node (ref "IC1") (pin "15") (pinfunction "PIO0_4/SCL_15") (pintype "bidirectional"))
    )
    (net (code "182") (name "unconnected-(IC1-PIO0_5{slash}SDA-Pad16)") (class "Default")
      (node (ref "IC1") (pin "16") (pinfunction "PIO0_5/SDA_16") (pintype "bidirectional"))
    )
    (net (code "183") (name "unconnected-(IC1-PIO0_6{slash}SCK0-Pad22)") (class "Default")
      (node (ref "IC1") (pin "22") (pinfunction "PIO0_6/SCK0_22") (pintype "bidirectional"))
    )
    (net (code "184") (name "unconnected-(IC1-PIO0_7{slash}~{CTS}-Pad23)") (class "Default")
      (node (ref "IC1") (pin "23") (pinfunction "PIO0_7/~{CTS}_23") (pintype "bidirectional"))
    )
    (net (code "185") (name "unconnected-(IC1-PIO0_8{slash}MISO0{slash}CT16B0_MAT0-Pad27)") (class "Default")
      (node (ref "IC1") (pin "27") (pinfunction "PIO0_8/MISO0/CT16B0_MAT0_27") (pintype "bidirectional"))
    )
    (net (code "186") (name "unconnected-(IC1-PIO0_9{slash}MOSI0{slash}CT16B0_MAT1-Pad28)") (class "Default")
      (node (ref "IC1") (pin "28") (pinfunction "PIO0_9/MOSI0/CT16B0_MAT1_28") (pintype "bidirectional"))
    )
    (net (code "187") (name "unconnected-(IC1-PIO1_2{slash}AD3{slash}CT32B1_MAT1-Pad35)") (class "Default")
      (node (ref "IC1") (pin "35") (pinfunction "PIO1_2/AD3/CT32B1_MAT1_35") (pintype "bidirectional"))
    )
    (net (code "188") (name "unconnected-(IC1-PIO1_4{slash}AD5{slash}CT32B1_MAT3-Pad40)") (class "Default")
      (node (ref "IC1") (pin "40") (pinfunction "PIO1_4/AD5/CT32B1_MAT3_40") (pintype "bidirectional"))
    )
    (net (code "189") (name "unconnected-(IC1-PIO1_5{slash}~{RTS}{slash}CT32B0_CAP0-Pad45)") (class "Default")
      (node (ref "IC1") (pin "45") (pinfunction "PIO1_5/~{RTS}/CT32B0_CAP0_45") (pintype "bidirectional"))
    )
    (net (code "190") (name "unconnected-(IC1-PIO1_6{slash}RXD{slash}CT32B0_MAT0-Pad46)") (class "Default")
      (node (ref "IC1") (pin "46") (pinfunction "PIO1_6/RXD/CT32B0_MAT0_46") (pintype "bidirectional"))
    )
    (net (code "191") (name "unconnected-(IC1-PIO1_7{slash}TXD{slash}CT32B0_MAT1-Pad47)") (class "Default")
      (node (ref "IC1") (pin "47") (pinfunction "PIO1_7/TXD/CT32B0_MAT1_47") (pintype "bidirectional"))
    )
    (net (code "192") (name "unconnected-(IC1-PIO1_8{slash}CT16B1_CAP0-Pad9)") (class "Default")
      (node (ref "IC1") (pin "9") (pinfunction "PIO1_8/CT16B1_CAP0_9") (pintype "bidirectional"))
    )
    (net (code "193") (name "unconnected-(IC1-PIO1_9{slash}CT16B1_MAT0-Pad17)") (class "Default")
      (node (ref "IC1") (pin "17") (pinfunction "PIO1_9/CT16B1_MAT0_17") (pintype "bidirectional"))
    )
    (net (code "194") (name "unconnected-(IC1-PIO1_10{slash}AD6{slash}CT16B1_MAT1-Pad30)") (class "Default")
      (node (ref "IC1") (pin "30") (pinfunction "PIO1_10/AD6/CT16B1_MAT1_30") (pintype "bidirectional"))
    )
    (net (code "195") (name "unconnected-(IC1-PIO1_11{slash}AD7-Pad42)") (class "Default")
      (node (ref "IC1") (pin "42") (pinfunction "PIO1_11/AD7_42") (pintype "bidirectional"))
    )
    (net (code "196") (name "unconnected-(IC1-PIO2_4-Pad18)") (class "Default")
      (node (ref "IC1") (pin "18") (pinfunction "PIO2_4_18") (pintype "bidirectional"))
    )
    (net (code "197") (name "unconnected-(IC1-PIO2_5-Pad21)") (class "Default")
      (node (ref "IC1") (pin "21") (pinfunction "PIO2_5_21") (pintype "bidirectional"))
    )
    (net (code "198") (name "unconnected-(IC1-PIO2_6-Pad1)") (class "Default")
      (node (ref "IC1") (pin "1") (pinfunction "PIO2_6_1") (pintype "bidirectional"))
    )
    (net (code "199") (name "unconnected-(IC1-PIO2_7-Pad11)") (class "Default")
      (node (ref "IC1") (pin "11") (pinfunction "PIO2_7_11") (pintype "bidirectional"))
    )
    (net (code "200") (name "unconnected-(IC1-PIO2_8-Pad12)") (class "Default")
      (node (ref "IC1") (pin "12") (pinfunction "PIO2_8_12") (pintype "bidirectional"))
    )
    (net (code "201") (name "unconnected-(IC1-PIO2_9-Pad24)") (class "Default")
      (node (ref "IC1") (pin "24") (pinfunction "PIO2_9_24") (pintype "bidirectional"))
    )
    (net (code "202") (name "unconnected-(IC1-PIO2_10-Pad25)") (class "Default")
      (node (ref "IC1") (pin "25") (pinfunction "PIO2_10_25") (pintype "bidirectional"))
    )
    (net (code "203") (name "unconnected-(IC1-PIO2_11{slash}SCK0-Pad31)") (class "Default")
      (node (ref "IC1") (pin "31") (pinfunction "PIO2_11/SCK0_31") (pintype "bidirectional"))
    )
    (net (code "204") (name "unconnected-(IC1-PIO3_0{slash}~{DTR}-Pad36)") (class "Default")
      (node (ref "IC1") (pin "36") (pinfunction "PIO3_0/~{DTR}_36") (pintype "bidirectional"))
    )
    (net (code "205") (name "unconnected-(IC1-PIO3_1{slash}~{DSR}-Pad37)") (class "Default")
      (node (ref "IC1") (pin "37") (pinfunction "PIO3_1/~{DSR}_37") (pintype "bidirectional"))
    )
    (net (code "206") (name "unconnected-(IC1-PIO3_2{slash}~{DCD}-Pad43)") (class "Default")
      (node (ref "IC1") (pin "43") (pinfunction "PIO3_2/~{DCD}_43") (pintype "bidirectional"))
    )
    (net (code "207") (name "unconnected-(IC2-S9-Pad9)") (class "Default")
      (node (ref "IC2") (pin "9") (pinfunction "S9_9") (pintype "bidirectional"))
    )
    (net (code "208") (name "unconnected-(IC2-S10-Pad7)") (class "Default")
      (node (ref "IC2") (pin "7") (pinfunction "S10_7") (pintype "bidirectional"))
    )
    (net (code "209") (name "unconnected-(IC2-S11-Pad5)") (class "Default")
      (node (ref "IC2") (pin "5") (pinfunction "S11_5") (pintype "bidirectional"))
    )
    (net (code "210") (name "unconnected-(IC2-S12-Pad3)") (class "Default")
      (node (ref "IC2") (pin "3") (pinfunction "S12_3") (pintype "bidirectional"))
    )
    (net (code "211") (name "unconnected-(IC4-VRF-Pad5)") (class "Default")
      (node (ref "IC4") (pin "5") (pinfunction "VRF_5") (pintype "bidirectional"))
    )
    (net (code "212") (name "unconnected-(IC5-VRF-Pad5)") (class "Default")
      (node (ref "IC5") (pin "5") (pinfunction "VRF_5") (pintype "bidirectional"))
    )
    (net (code "213") (name "unconnected-(IC7-PIO0_2{slash}SSEL{slash}CT16B0_CAP0-Pad10)") (class "Default")
      (node (ref "IC7") (pin "10") (pinfunction "PIO0_2/SSEL/CT16B0_CAP0_10") (pintype "bidirectional"))
    )
    (net (code "214") (name "unconnected-(IC7-PIO0_4{slash}SCL-Pad15)") (class "Default")
      (node (ref "IC7") (pin "15") (pinfunction "PIO0_4/SCL_15") (pintype "bidirectional"))
    )
    (net (code "215") (name "unconnected-(IC7-PIO0_5{slash}SDA-Pad16)") (class "Default")
      (node (ref "IC7") (pin "16") (pinfunction "PIO0_5/SDA_16") (pintype "bidirectional"))
    )
    (net (code "216") (name "unconnected-(IC7-PIO0_6{slash}SCK0-Pad22)") (class "Default")
      (node (ref "IC7") (pin "22") (pinfunction "PIO0_6/SCK0_22") (pintype "bidirectional"))
    )
    (net (code "217") (name "unconnected-(IC7-PIO0_7{slash}~{CTS}-Pad23)") (class "Default")
      (node (ref "IC7") (pin "23") (pinfunction "PIO0_7/~{CTS}_23") (pintype "bidirectional"))
    )
    (net (code "218") (name "unconnected-(IC7-PIO0_8{slash}MISO0{slash}CT16B0_MAT0-Pad27)") (class "Default")
      (node (ref "IC7") (pin "27") (pinfunction "PIO0_8/MISO0/CT16B0_MAT0_27") (pintype "bidirectional"))
    )
    (net (code "219") (name "unconnected-(IC7-PIO0_9{slash}MOSI0{slash}CT16B0_MAT1-Pad28)") (class "Default")
      (node (ref "IC7") (pin "28") (pinfunction "PIO0_9/MOSI0/CT16B0_MAT1_28") (pintype "bidirectional"))
    )
    (net (code "220") (name "unconnected-(IC7-PIO1_2{slash}AD3{slash}CT32B1_MAT1-Pad35)") (class "Default")
      (node (ref "IC7") (pin "35") (pinfunction "PIO1_2/AD3/CT32B1_MAT1_35") (pintype "bidirectional"))
    )
    (net (code "221") (name "unconnected-(IC7-PIO1_4{slash}AD5{slash}CT32B1_MAT3-Pad40)") (class "Default")
      (node (ref "IC7") (pin "40") (pinfunction "PIO1_4/AD5/CT32B1_MAT3_40") (pintype "bidirectional"))
    )
    (net (code "222") (name "unconnected-(IC7-PIO1_5{slash}~{RTS}{slash}CT32B0_CAP0-Pad45)") (class "Default")
      (node (ref "IC7") (pin "45") (pinfunction "PIO1_5/~{RTS}/CT32B0_CAP0_45") (pintype "bidirectional"))
    )
    (net (code "223") (name "unconnected-(IC7-PIO1_6{slash}RXD{slash}CT32B0_MAT0-Pad46)") (class "Default")
      (node (ref "IC7") (pin "46") (pinfunction "PIO1_6/RXD/CT32B0_MAT0_46") (pintype "bidirectional"))
    )
    (net (code "224") (name "unconnected-(IC7-PIO1_7{slash}TXD{slash}CT32B0_MAT1-Pad47)") (class "Default")
      (node (ref "IC7") (pin "47") (pinfunction "PIO1_7/TXD/CT32B0_MAT1_47") (pintype "bidirectional"))
    )
    (net (code "225") (name "unconnected-(IC7-PIO1_8{slash}CT16B1_CAP0-Pad9)") (class "Default")
      (node (ref "IC7") (pin "9") (pinfunction "PIO1_8/CT16B1_CAP0_9") (pintype "bidirectional"))
    )
    (net (code "226") (name "unconnected-(IC7-PIO1_9{slash}CT16B1_MAT0-Pad17)") (class "Default")
      (node (ref "IC7") (pin "17") (pinfunction "PIO1_9/CT16B1_MAT0_17") (pintype "bidirectional"))
    )
    (net (code "227") (name "unconnected-(IC7-PIO1_10{slash}AD6{slash}CT16B1_MAT1-Pad30)") (class "Default")
      (node (ref "IC7") (pin "30") (pinfunction "PIO1_10/AD6/CT16B1_MAT1_30") (pintype "bidirectional"))
    )
    (net (code "228") (name "unconnected-(IC7-PIO1_11{slash}AD7-Pad42)") (class "Default")
      (node (ref "IC7") (pin "42") (pinfunction "PIO1_11/AD7_42") (pintype "bidirectional"))
    )
    (net (code "229") (name "unconnected-(IC7-PIO2_4-Pad18)") (class "Default")
      (node (ref "IC7") (pin "18") (pinfunction "PIO2_4_18") (pintype "bidirectional"))
    )
    (net (code "230") (name "unconnected-(IC7-PIO2_5-Pad21)") (class "Default")
      (node (ref "IC7") (pin "21") (pinfunction "PIO2_5_21") (pintype "bidirectional"))
    )
    (net (code "231") (name "unconnected-(IC7-PIO2_6-Pad1)") (class "Default")
      (node (ref "IC7") (pin "1") (pinfunction "PIO2_6_1") (pintype "bidirectional"))
    )
    (net (code "232") (name "unconnected-(IC7-PIO2_7-Pad11)") (class "Default")
      (node (ref "IC7") (pin "11") (pinfunction "PIO2_7_11") (pintype "bidirectional"))
    )
    (net (code "233") (name "unconnected-(IC7-PIO2_8-Pad12)") (class "Default")
      (node (ref "IC7") (pin "12") (pinfunction "PIO2_8_12") (pintype "bidirectional"))
    )
    (net (code "234") (name "unconnected-(IC7-PIO2_9-Pad24)") (class "Default")
      (node (ref "IC7") (pin "24") (pinfunction "PIO2_9_24") (pintype "bidirectional"))
    )
    (net (code "235") (name "unconnected-(IC7-PIO2_10-Pad25)") (class "Default")
      (node (ref "IC7") (pin "25") (pinfunction "PIO2_10_25") (pintype "bidirectional"))
    )
    (net (code "236") (name "unconnected-(IC7-PIO2_11{slash}SCK0-Pad31)") (class "Default")
      (node (ref "IC7") (pin "31") (pinfunction "PIO2_11/SCK0_31") (pintype "bidirectional"))
    )
    (net (code "237") (name "unconnected-(IC7-PIO3_0{slash}~{DTR}-Pad36)") (class "Default")
      (node (ref "IC7") (pin "36") (pinfunction "PIO3_0/~{DTR}_36") (pintype "bidirectional"))
    )
    (net (code "238") (name "unconnected-(IC7-PIO3_1{slash}~{DSR}-Pad37)") (class "Default")
      (node (ref "IC7") (pin "37") (pinfunction "PIO3_1/~{DSR}_37") (pintype "bidirectional"))
    )
    (net (code "239") (name "unconnected-(IC7-PIO3_2{slash}~{DCD}-Pad43)") (class "Default")
      (node (ref "IC7") (pin "43") (pinfunction "PIO3_2/~{DCD}_43") (pintype "bidirectional"))
    )
    (net (code "240") (name "unconnected-(IC8-S9-Pad9)") (class "Default")
      (node (ref "IC8") (pin "9") (pinfunction "S9_9") (pintype "bidirectional"))
    )
    (net (code "241") (name "unconnected-(IC8-S10-Pad7)") (class "Default")
      (node (ref "IC8") (pin "7") (pinfunction "S10_7") (pintype "bidirectional"))
    )
    (net (code "242") (name "unconnected-(IC8-S11-Pad5)") (class "Default")
      (node (ref "IC8") (pin "5") (pinfunction "S11_5") (pintype "bidirectional"))
    )
    (net (code "243") (name "unconnected-(IC8-S12-Pad3)") (class "Default")
      (node (ref "IC8") (pin "3") (pinfunction "S12_3") (pintype "bidirectional"))
    )
  )
)
